# Mk3_Prototype2.net
KiCad netlist of a schematic drawn in EAGLE
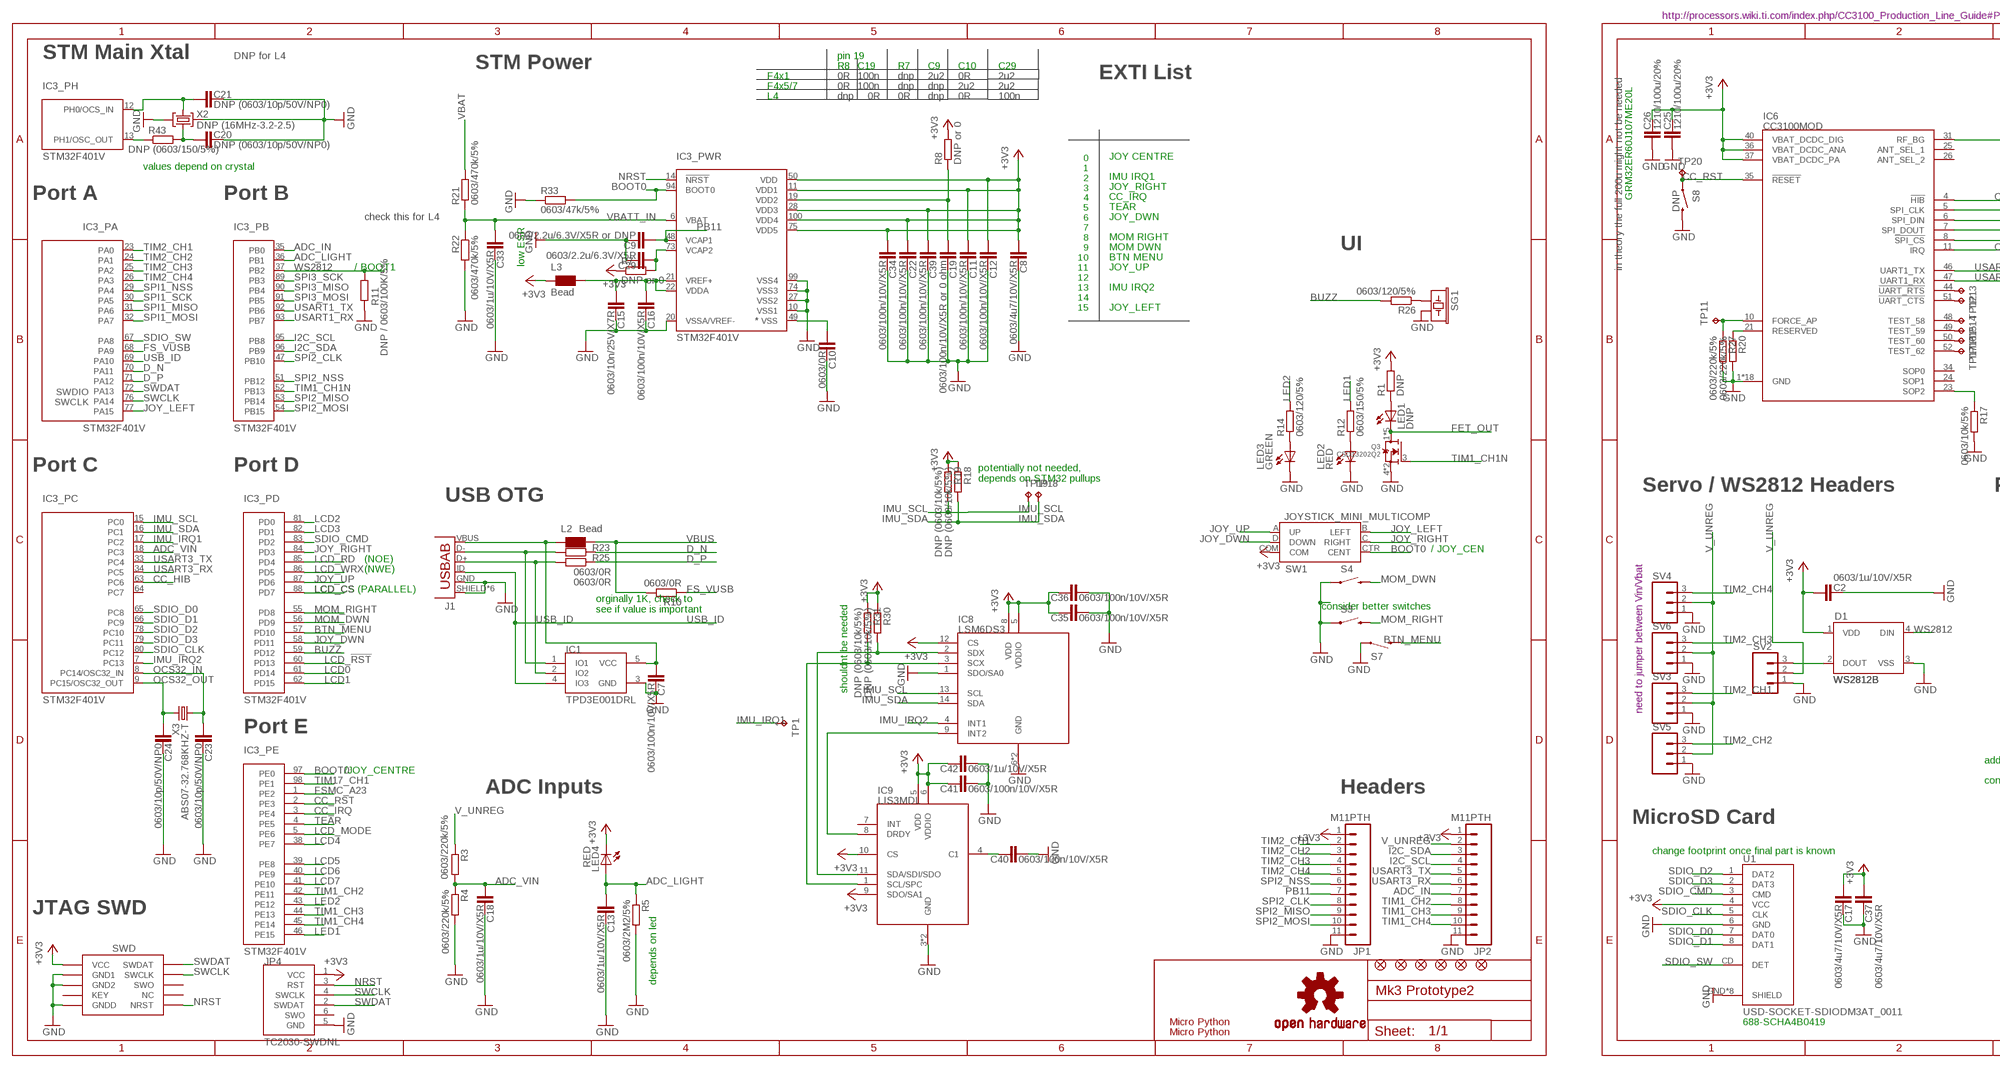
[diagram p0: schematic, sheet 1, part 1 of 2]
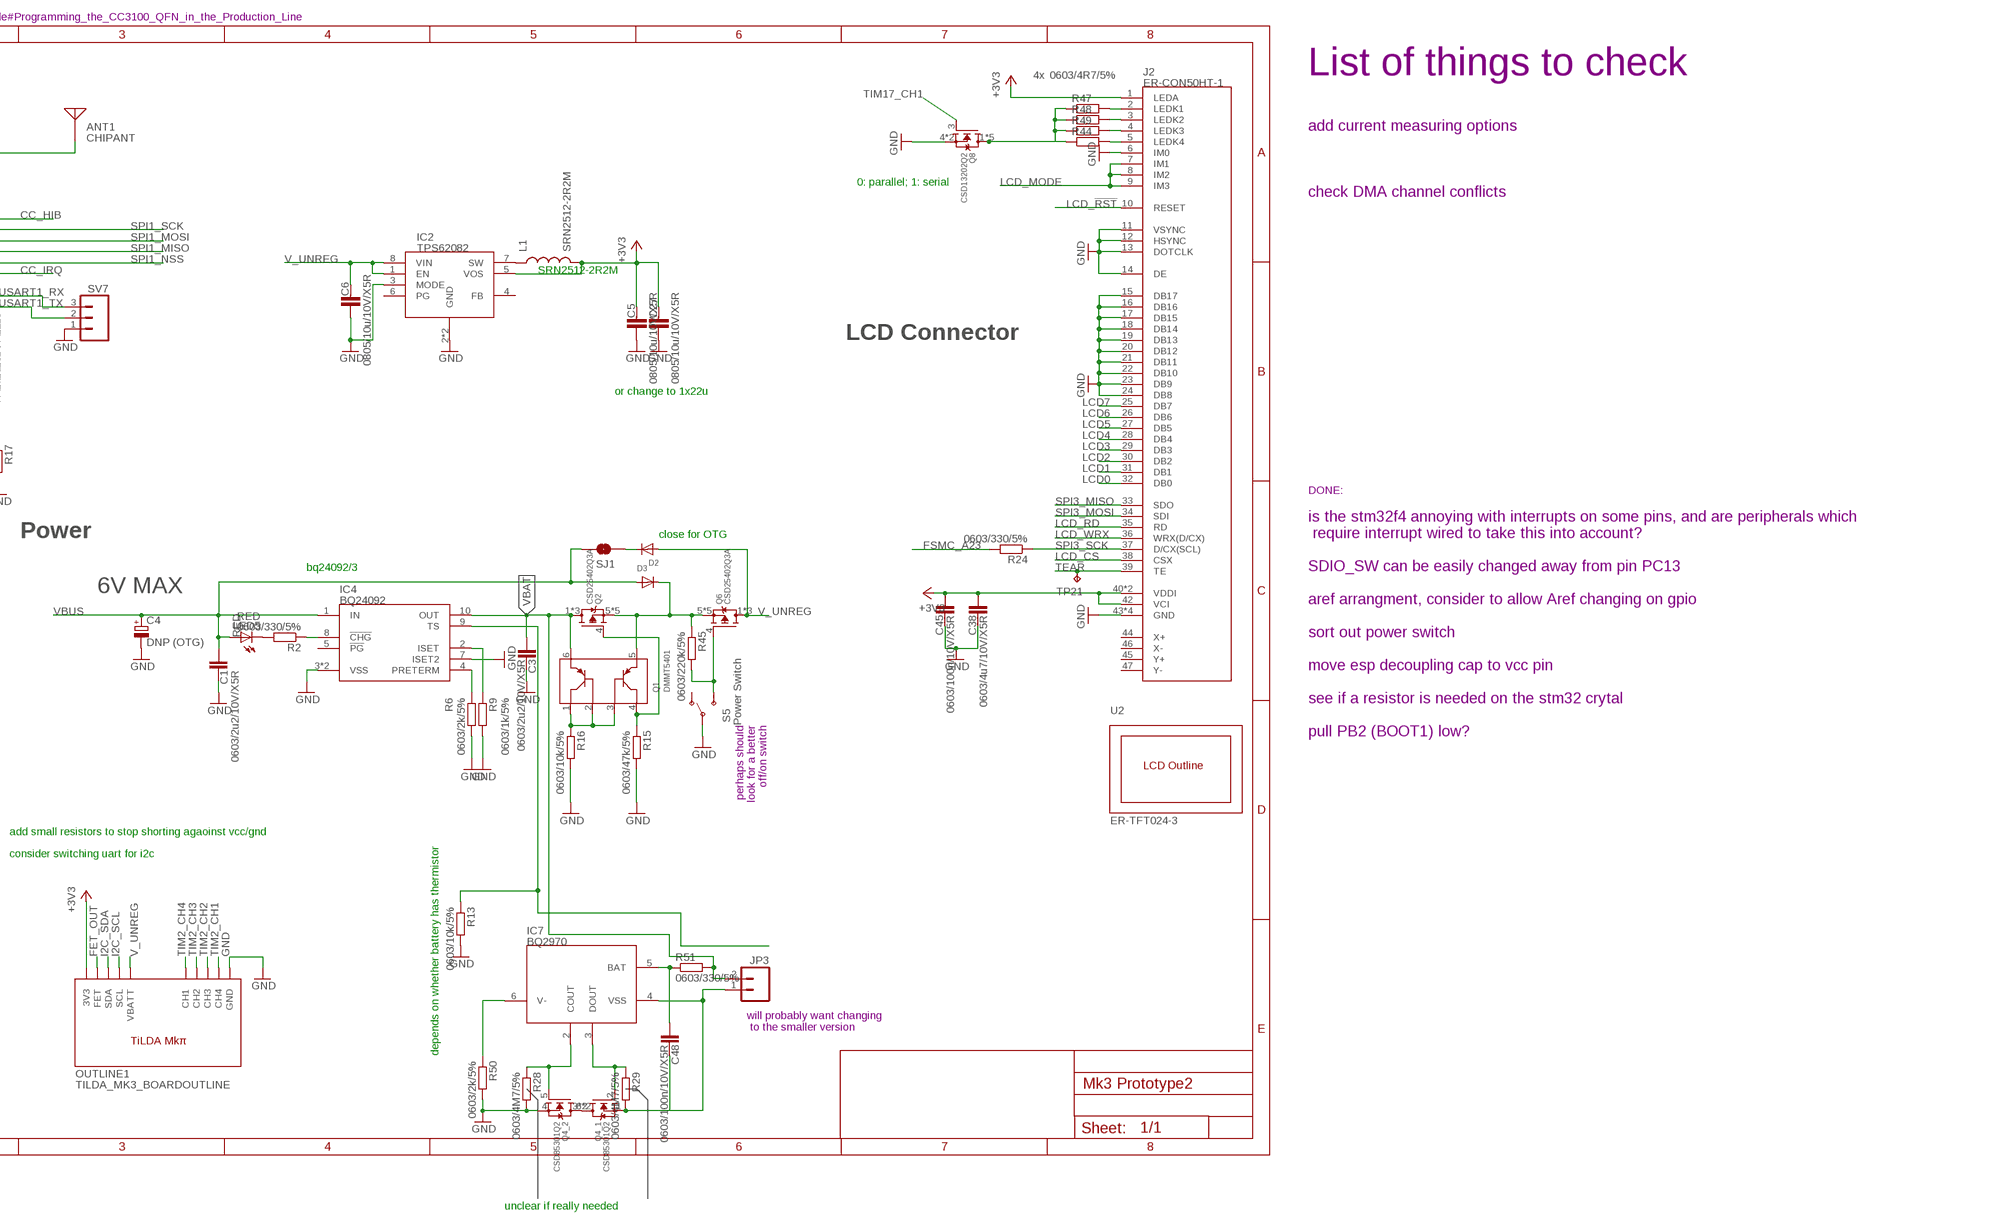
[diagram p1: schematic, sheet 1, part 2 of 2]

(export (version "E")
  (design (tool "Eeschema 10.0.6"))
  (components
    (comp (ref "ANT1")
      (value "CHIPANT")
      (footprint "eagle-import:2450AT42A100")
      (libsource (lib "eagle-import") (part "CHIPANT"))
    )
    (comp (ref "C1")
      (value "0603/2u2/10V/X5R")
      (footprint "eagle-import:C0603K-SMALL")
      (libsource (lib "eagle-import") (part "C-EUC0603K-SMALL"))
    )
    (comp (ref "C2")
      (value "0603/1u/10V/X5R")
      (footprint "eagle-import:C0603K-SMALL")
      (libsource (lib "eagle-import") (part "C-EUC0603K-SMALL"))
    )
    (comp (ref "C3")
      (value "0603/2u2/10V/X5R")
      (footprint "eagle-import:C0603K-SMALL")
      (libsource (lib "eagle-import") (part "C-EUC0603K-SMALL"))
    )
    (comp (ref "C4")
      (value "DNP (OTG)")
      (footprint "eagle-import:E2,5-6")
      (libsource (lib "eagle-import") (part "CPOL-EUE2.5-6"))
    )
    (comp (ref "C5")
      (value "0805/10u/10V/X5R")
      (footprint "eagle-import:C0805-N")
      (libsource (lib "eagle-import") (part "CAPACITOR0805-N"))
    )
    (comp (ref "C6")
      (value "0805/10u/10V/X5R")
      (footprint "eagle-import:C0805-N")
      (libsource (lib "eagle-import") (part "CAPACITOR0805-N"))
    )
    (comp (ref "C7")
      (value "0603/100n/10V/X5R")
      (footprint "eagle-import:C0603K-SMALL")
      (libsource (lib "eagle-import") (part "C-EUC0603K-SMALL"))
    )
    (comp (ref "C8")
      (value "0603/4u7/10V/X5R")
      (footprint "eagle-import:C0603K-SMALL")
      (libsource (lib "eagle-import") (part "C-EUC0603K-SMALL"))
    )
    (comp (ref "C9")
      (value "0603/2.2u/6.3V/X5R or DNP")
      (footprint "eagle-import:C0603K-SMALL")
      (libsource (lib "eagle-import") (part "C-EUC0603K-SMALL"))
    )
    (comp (ref "C10")
      (value "0603/0R")
      (footprint "eagle-import:C0603K-SMALL")
      (libsource (lib "eagle-import") (part "C-EUC0603K-SMALL"))
    )
    (comp (ref "C11")
      (value "0603/100n/10V/X5R")
      (footprint "eagle-import:C0603K-SMALL")
      (libsource (lib "eagle-import") (part "C-EUC0603K-SMALL"))
    )
    (comp (ref "C12")
      (value "0603/100n/10V/X5R")
      (footprint "eagle-import:C0603K-SMALL")
      (libsource (lib "eagle-import") (part "C-EUC0603K-SMALL"))
    )
    (comp (ref "C13")
      (value "0603/1u/10V/X5R")
      (footprint "eagle-import:C0603K-SMALL")
      (libsource (lib "eagle-import") (part "C-EUC0603K-SMALL"))
    )
    (comp (ref "C15")
      (value "0603/10n/25V/X7R")
      (footprint "eagle-import:C0603K-SMALL")
      (libsource (lib "eagle-import") (part "C-EUC0603K-SMALL"))
    )
    (comp (ref "C16")
      (value "0603/100n/10V/X5R")
      (footprint "eagle-import:C0603K-SMALL")
      (libsource (lib "eagle-import") (part "C-EUC0603K-SMALL"))
    )
    (comp (ref "C17")
      (value "0603/4u7/10V/X5R")
      (footprint "eagle-import:C0603K-SMALL")
      (libsource (lib "eagle-import") (part "C-EUC0603K-SMALL"))
    )
    (comp (ref "C18")
      (value "0603/1u/10V/X5R")
      (footprint "eagle-import:C0603K-SMALL")
      (libsource (lib "eagle-import") (part "C-EUC0603K-SMALL"))
    )
    (comp (ref "C19")
      (value "0603/100n/10V/X5R or 0 ohm")
      (footprint "eagle-import:C0603K-SMALL")
      (libsource (lib "eagle-import") (part "C-EUC0603K-SMALL"))
    )
    (comp (ref "C20")
      (value "DNP (0603/10p/50V/NP0)")
      (footprint "eagle-import:C0603K-SMALL")
      (libsource (lib "eagle-import") (part "C-EUC0603K-SMALL"))
    )
    (comp (ref "C21")
      (value "DNP (0603/10p/50V/NP0)")
      (footprint "eagle-import:C0603K-SMALL")
      (libsource (lib "eagle-import") (part "C-EUC0603K-SMALL"))
    )
    (comp (ref "C22")
      (value "0603/100n/10V/X5R")
      (footprint "eagle-import:C0603K-SMALL")
      (libsource (lib "eagle-import") (part "C-EUC0603K-SMALL"))
    )
    (comp (ref "C23")
      (value "0603/10p/50V/NP0")
      (footprint "eagle-import:C0603K-SMALL")
      (libsource (lib "eagle-import") (part "C-EUC0603K-SMALL"))
    )
    (comp (ref "C24")
      (value "0603/10p/50V/NP0")
      (footprint "eagle-import:C0603K-SMALL")
      (libsource (lib "eagle-import") (part "C-EUC0603K-SMALL"))
    )
    (comp (ref "C25")
      (value "1210/100u/20%")
      (footprint "eagle-import:C1210K")
      (libsource (lib "eagle-import") (part "C-EUC1210K"))
    )
    (comp (ref "C26")
      (value "1210/100u/20%")
      (footprint "eagle-import:C1210K")
      (libsource (lib "eagle-import") (part "C-EUC1210K"))
    )
    (comp (ref "C27")
      (value "0805/10u/10V/X5R")
      (footprint "eagle-import:C0805-N")
      (libsource (lib "eagle-import") (part "CAPACITOR0805-N"))
    )
    (comp (ref "C29")
      (value "0603/2.2u/6.3V/X5R")
      (footprint "eagle-import:C0603K-SMALL")
      (libsource (lib "eagle-import") (part "C-EUC0603K-SMALL"))
    )
    (comp (ref "C33")
      (value "0603/1u/10V/X5R")
      (footprint "eagle-import:C0603K-SMALL")
      (libsource (lib "eagle-import") (part "C-EUC0603K-SMALL"))
    )
    (comp (ref "C34")
      (value "0603/100n/10V/X5R")
      (footprint "eagle-import:C0603K-SMALL")
      (libsource (lib "eagle-import") (part "C-EUC0603K-SMALL"))
    )
    (comp (ref "C35")
      (value "0603/100n/10V/X5R")
      (footprint "eagle-import:C0603K-SMALL")
      (libsource (lib "eagle-import") (part "C-EUC0603K-SMALL"))
    )
    (comp (ref "C36")
      (value "0603/100n/10V/X5R")
      (footprint "eagle-import:C0603K-SMALL")
      (libsource (lib "eagle-import") (part "C-EUC0603K-SMALL"))
    )
    (comp (ref "C37")
      (value "0603/4u7/10V/X5R")
      (footprint "eagle-import:C0603K-SMALL")
      (libsource (lib "eagle-import") (part "C-EUC0603K-SMALL"))
    )
    (comp (ref "C38")
      (value "0603/4u7/10V/X5R")
      (footprint "eagle-import:C0603K-SMALL")
      (libsource (lib "eagle-import") (part "C-EUC0603K-SMALL"))
    )
    (comp (ref "C39")
      (value "0603/100n/10V/X5R")
      (footprint "eagle-import:C0603K-SMALL")
      (libsource (lib "eagle-import") (part "C-EUC0603K-SMALL"))
    )
    (comp (ref "C40")
      (value "0603/100n/10V/X5R")
      (footprint "eagle-import:C0603K-SMALL")
      (libsource (lib "eagle-import") (part "C-EUC0603K-SMALL"))
    )
    (comp (ref "C41")
      (value "0603/100n/10V/X5R")
      (footprint "eagle-import:C0603K-SMALL")
      (libsource (lib "eagle-import") (part "C-EUC0603K-SMALL"))
    )
    (comp (ref "C42")
      (value "0603/1u/10V/X5R")
      (footprint "eagle-import:C0603K-SMALL")
      (libsource (lib "eagle-import") (part "C-EUC0603K-SMALL"))
    )
    (comp (ref "C45")
      (value "0603/100n/10V/X5R")
      (footprint "eagle-import:C0603K-SMALL")
      (libsource (lib "eagle-import") (part "C-EUC0603K-SMALL"))
    )
    (comp (ref "C48")
      (value "0603/100n/10V/X5R")
      (footprint "eagle-import:C0603K-SMALL")
      (libsource (lib "eagle-import") (part "C-EUC0603K-SMALL"))
    )
    (comp (ref "D1")
      (value "WS2812B")
      (footprint "eagle-import:WS2812B")
      (libsource (lib "eagle-import") (part "WS2812B"))
    )
    (comp (ref "D2")
      (value "DIODESOD-323F")
      (footprint "eagle-import:SOD-323F")
      (libsource (lib "eagle-import") (part "DIODESOD-323F"))
    )
    (comp (ref "D3")
      (value "DIODESOD-323F")
      (footprint "eagle-import:SOD-323F")
      (libsource (lib "eagle-import") (part "DIODESOD-323F"))
    )
    (comp (ref "FID1")
      (value "FIDUCIAL1X2.5-STOP")
      (footprint "eagle-import:FIDUCIAL-1X2.5-STOP")
      (libsource (lib "eagle-import") (part "FIDUCIAL1X2.5-STOP"))
    )
    (comp (ref "FID2")
      (value "FIDUCIAL1X2.5-STOP")
      (footprint "eagle-import:FIDUCIAL-1X2.5-STOP")
      (libsource (lib "eagle-import") (part "FIDUCIAL1X2.5-STOP"))
    )
    (comp (ref "FID3")
      (value "FIDUCIAL1X2.5-STOP")
      (footprint "eagle-import:FIDUCIAL-1X2.5-STOP")
      (libsource (lib "eagle-import") (part "FIDUCIAL1X2.5-STOP"))
    )
    (comp (ref "FID4")
      (value "FIDUCIAL1X2.5-STOP")
      (footprint "eagle-import:FIDUCIAL-1X2.5-STOP")
      (libsource (lib "eagle-import") (part "FIDUCIAL1X2.5-STOP"))
    )
    (comp (ref "FID5")
      (value "FIDUCIAL1X2.5-STOP")
      (footprint "eagle-import:FIDUCIAL-1X2.5-STOP")
      (libsource (lib "eagle-import") (part "FIDUCIAL1X2.5-STOP"))
    )
    (comp (ref "FID6")
      (value "FIDUCIAL1X2.5-STOP")
      (footprint "eagle-import:FIDUCIAL-1X2.5-STOP")
      (libsource (lib "eagle-import") (part "FIDUCIAL1X2.5-STOP"))
    )
    (comp (ref "IC1")
      (value "TPD3E001DRL")
      (footprint "eagle-import:DRL-5")
      (libsource (lib "eagle-import") (part "TPD3E001DRL"))
    )
    (comp (ref "IC2")
      (value "TPS62082")
      (footprint "eagle-import:WSON8")
      (libsource (lib "eagle-import") (part "TPS62082"))
    )
    (comp (ref "IC3")
      (value "STM32F401V")
      (footprint "eagle-import:TQFP100")
      (fields (field (name "FARNELL") "2432116"))
      (libsource (lib "eagle-import") (part "STM32F401V"))
    )
    (comp (ref "IC4")
      (value "BQ24092")
      (footprint "eagle-import:HVSSOP10")
      (libsource (lib "eagle-import") (part "BQ2409X"))
    )
    (comp (ref "IC6")
      (value "CC3100MOD")
      (footprint "eagle-import:CC3100MOD")
      (libsource (lib "eagle-import") (part "CC3100MOD"))
    )
    (comp (ref "IC7")
      (value "BQ2970")
      (footprint "eagle-import:WSON-6")
      (libsource (lib "eagle-import") (part "BQ2970"))
    )
    (comp (ref "IC8")
      (value "LSM6DS3")
      (footprint "eagle-import:LGA14")
      (libsource (lib "eagle-import") (part "LSM6DS3"))
    )
    (comp (ref "IC9")
      (value "LIS3MDL")
      (footprint "eagle-import:LGA12")
      (libsource (lib "eagle-import") (part "LIS3MDL"))
    )
    (comp (ref "J1")
      (value "ZX62-AB-5PA(11)")
      (footprint "eagle-import:USB-AB-MICRO-SMD_LWK")
      (libsource (lib "eagle-import") (part "USB-AB-LWK"))
    )
    (comp (ref "J2")
      (value "ER-CON50HT-1")
      (footprint "eagle-import:FH12-50S-0.5SH")
      (libsource (lib "eagle-import") (part "ER-TFT024-3"))
    )
    (comp (ref "J3")
      (value "SWD_SHROUD")
      (footprint "eagle-import:SWD_PTH_SHROUD")
      (libsource (lib "eagle-import") (part "SWD_SHROUD"))
    )
    (comp (ref "JP1")
      (value "M11PTH")
      (footprint "eagle-import:1X11")
      (libsource (lib "eagle-import") (part "M11PTH"))
    )
    (comp (ref "JP2")
      (value "M11PTH")
      (footprint "eagle-import:1X11")
      (libsource (lib "eagle-import") (part "M11PTH"))
    )
    (comp (ref "JP3")
      (value "M02-JST-2MM-SMT")
      (footprint "eagle-import:JST-2-SMD")
      (libsource (lib "eagle-import") (part "M02-JST-2MM-SMT"))
    )
    (comp (ref "JP4")
      (value "TC2030-SWDNL")
      (footprint "eagle-import:TC2030-MCP-NL")
      (libsource (lib "eagle-import") (part "TC2030-SWDNL"))
    )
    (comp (ref "L1")
      (value "SRN2512-2R2M")
      (footprint "eagle-import:1008")
      (libsource (lib "eagle-import") (part "INDUCTOR1008"))
    )
    (comp (ref "L2")
      (value "Bead")
      (footprint "eagle-import:WUERTH-0805")
      (libsource (lib "eagle-import") (part "WE-CBF_0805"))
    )
    (comp (ref "L3")
      (value "Bead")
      (footprint "eagle-import:WUERTH-0805")
      (libsource (lib "eagle-import") (part "WE-CBF_0805"))
    )
    (comp (ref "LED1")
      (value "DNP")
      (footprint "eagle-import:LED5MM")
      (libsource (lib "eagle-import") (part "LED5MM"))
    )
    (comp (ref "LED2")
      (value "RED")
      (footprint "eagle-import:LED-0603-CORRECT")
      (fields (field (name "COLOUR") "RED"))
      (libsource (lib "eagle-import") (part "LED0603-CORRECT"))
    )
    (comp (ref "LED3")
      (value "GREEN")
      (footprint "eagle-import:LED-0603-CORRECT")
      (fields (field (name "COLOUR") "GREEN"))
      (libsource (lib "eagle-import") (part "LED0603-CORRECT"))
    )
    (comp (ref "LED4")
      (value "RED")
      (footprint "eagle-import:LED-0603-CORRECT")
      (libsource (lib "eagle-import") (part "LED0603-CORRECT"))
    )
    (comp (ref "LED5")
      (value "RED")
      (footprint "eagle-import:LED-0603-CORRECT")
      (fields (field (name "COLOUR") "RED"))
      (libsource (lib "eagle-import") (part "LED0603-CORRECT"))
    )
    (comp (ref "LOGO1")
      (value "OSHW-LOGOM")
      (footprint "eagle-import:OSHW-LOGO-M")
      (libsource (lib "eagle-import") (part "OSHW-LOGOM"))
    )
    (comp (ref "LOGO2")
      (value "MICROPYTHON-SILK")
      (footprint "eagle-import:UPYTHON_LOGO_SLIKONLY")
      (libsource (lib "eagle-import") (part "MICROPYTHON-SILK"))
    )
    (comp (ref "LOGO3")
      (value "MICROPYTHON-STOP")
      (footprint "eagle-import:UPYTHON_LOGO_STOPONLY")
      (libsource (lib "eagle-import") (part "MICROPYTHON-STOP"))
    )
    (comp (ref "OUTLINE1")
      (value "TILDA_MK3_BOARDOUTLINE")
      (footprint "eagle-import:TILDA_MKE_OUTLINE")
      (libsource (lib "eagle-import") (part "TILDA_MK3_BOARDOUTLINE"))
    )
    (comp (ref "Q1")
      (value "DMMT5401")
      (footprint "eagle-import:SOT26")
      (libsource (lib "eagle-import") (part "DMMT5401"))
    )
    (comp (ref "Q2")
      (value "CSD25402Q3A")
      (footprint "eagle-import:Q3A")
      (libsource (lib "eagle-import") (part "CSD25402Q3A"))
    )
    (comp (ref "Q3")
      (value "CSD13202Q2")
      (footprint "eagle-import:Q2")
      (libsource (lib "eagle-import") (part "CSD13202Q2"))
    )
    (comp (ref "Q4")
      (value "CSD85301Q2")
      (footprint "eagle-import:Q2_DUAL")
      (fields (field (name "FARNELL") "2470183"))
      (libsource (lib "eagle-import") (part "CSD85301Q2"))
    )
    (comp (ref "Q6")
      (value "CSD25402Q3A")
      (footprint "eagle-import:Q3A")
      (libsource (lib "eagle-import") (part "CSD25402Q3A"))
    )
    (comp (ref "Q8")
      (value "CSD13202Q2")
      (footprint "eagle-import:Q2")
      (libsource (lib "eagle-import") (part "CSD13202Q2"))
    )
    (comp (ref "R1")
      (value "DNP")
      (footprint "eagle-import:0207_10")
      (libsource (lib "eagle-import") (part "R-EU_0207/10"))
    )
    (comp (ref "R2")
      (value "0603/330/5%")
      (footprint "eagle-import:C0603K-SMALL")
      (libsource (lib "eagle-import") (part "R-EU_0603K-SMALL"))
    )
    (comp (ref "R3")
      (value "0603/220k/5%")
      (footprint "eagle-import:C0603K-SMALL")
      (libsource (lib "eagle-import") (part "R-EU_0603K-SMALL"))
    )
    (comp (ref "R4")
      (value "0603/220k/5%")
      (footprint "eagle-import:C0603K-SMALL")
      (libsource (lib "eagle-import") (part "R-EU_0603K-SMALL"))
    )
    (comp (ref "R5")
      (value "0603/2M2/5%")
      (footprint "eagle-import:C0603K-SMALL")
      (libsource (lib "eagle-import") (part "R-EU_0603K-SMALL"))
    )
    (comp (ref "R6")
      (value "0603/2k/5%")
      (footprint "eagle-import:C0603K-SMALL")
      (libsource (lib "eagle-import") (part "R-EU_0603K-SMALL"))
    )
    (comp (ref "R7")
      (value "DNP or 0")
      (footprint "eagle-import:C0603K-SMALL")
      (libsource (lib "eagle-import") (part "R-EU_0603K-SMALL"))
    )
    (comp (ref "R8")
      (value "DNP or 0")
      (footprint "eagle-import:C0603K-SMALL")
      (libsource (lib "eagle-import") (part "R-EU_0603K-SMALL"))
    )
    (comp (ref "R9")
      (value "0603/1k/5%")
      (footprint "eagle-import:C0603K-SMALL")
      (libsource (lib "eagle-import") (part "R-EU_0603K-SMALL"))
    )
    (comp (ref "R10")
      (value "0603/0R")
      (footprint "eagle-import:C0603K-SMALL")
      (libsource (lib "eagle-import") (part "R-EU_0603K-SMALL"))
    )
    (comp (ref "R11")
      (value "DNP / 0603/100K/5%")
      (footprint "eagle-import:C0603K-SMALL")
      (libsource (lib "eagle-import") (part "R-EU_0603K-SMALL"))
    )
    (comp (ref "R12")
      (value "0603/150/5%")
      (footprint "eagle-import:C0603K-SMALL")
      (libsource (lib "eagle-import") (part "R-EU_0603K-SMALL"))
    )
    (comp (ref "R13")
      (value "0603/10k/5%")
      (footprint "eagle-import:C0603K-SMALL")
      (libsource (lib "eagle-import") (part "R-EU_0603K-SMALL"))
    )
    (comp (ref "R14")
      (value "0603/120/5%")
      (footprint "eagle-import:C0603K-SMALL")
      (libsource (lib "eagle-import") (part "R-EU_0603K-SMALL"))
    )
    (comp (ref "R15")
      (value "0603/47k/5%")
      (footprint "eagle-import:C0603K-SMALL")
      (libsource (lib "eagle-import") (part "R-EU_0603K-SMALL"))
    )
    (comp (ref "R16")
      (value "0603/10k/5%")
      (footprint "eagle-import:C0603K-SMALL")
      (libsource (lib "eagle-import") (part "R-EU_0603K-SMALL"))
    )
    (comp (ref "R17")
      (value "0603/10k/5%")
      (footprint "eagle-import:C0603K-SMALL")
      (libsource (lib "eagle-import") (part "R-EU_0603K-SMALL"))
    )
    (comp (ref "R18")
      (value "DNP (0603/10k/5%)")
      (footprint "eagle-import:C0603K-SMALL")
      (libsource (lib "eagle-import") (part "R-EU_0603K-SMALL"))
    )
    (comp (ref "R19")
      (value "DNP (0603/10k/5%)")
      (footprint "eagle-import:C0603K-SMALL")
      (libsource (lib "eagle-import") (part "R-EU_0603K-SMALL"))
    )
    (comp (ref "R20")
      (value "0603/220k/5%")
      (footprint "eagle-import:C0603K-SMALL")
      (libsource (lib "eagle-import") (part "R-EU_0603K-SMALL"))
    )
    (comp (ref "R21")
      (value "0603/470k/5%")
      (footprint "eagle-import:C0603K-SMALL")
      (libsource (lib "eagle-import") (part "R-EU_0603K-SMALL"))
    )
    (comp (ref "R22")
      (value "0603/470k/5%")
      (footprint "eagle-import:C0603K-SMALL")
      (libsource (lib "eagle-import") (part "R-EU_0603K-SMALL"))
    )
    (comp (ref "R23")
      (value "0603/0R")
      (footprint "eagle-import:C0603K-SMALL")
      (libsource (lib "eagle-import") (part "R-EU_0603K-SMALL"))
    )
    (comp (ref "R24")
      (value "0603/330/5%")
      (footprint "eagle-import:C0603K-SMALL")
      (libsource (lib "eagle-import") (part "R-EU_0603K-SMALL"))
    )
    (comp (ref "R25")
      (value "0603/0R")
      (footprint "eagle-import:C0603K-SMALL")
      (libsource (lib "eagle-import") (part "R-EU_0603K-SMALL"))
    )
    (comp (ref "R26")
      (value "0603/120/5%")
      (footprint "eagle-import:C0603K-SMALL")
      (libsource (lib "eagle-import") (part "R-EU_0603K-SMALL"))
    )
    (comp (ref "R27")
      (value "0603/220k/5%")
      (footprint "eagle-import:C0603K-SMALL")
      (libsource (lib "eagle-import") (part "R-EU_0603K-SMALL"))
    )
    (comp (ref "R28")
      (value "0603/4M7/5%")
      (footprint "eagle-import:C0603K-SMALL")
      (libsource (lib "eagle-import") (part "R-EU_0603K-SMALL"))
    )
    (comp (ref "R29")
      (value "0603/4M7/5%")
      (footprint "eagle-import:C0603K-SMALL")
      (libsource (lib "eagle-import") (part "R-EU_0603K-SMALL"))
    )
    (comp (ref "R30")
      (value "DNP (0603/10k/5%)")
      (footprint "eagle-import:C0603K-SMALL")
      (libsource (lib "eagle-import") (part "R-EU_0603K-SMALL"))
    )
    (comp (ref "R31")
      (value "DNP (0603/10k/5%)")
      (footprint "eagle-import:C0603K-SMALL")
      (libsource (lib "eagle-import") (part "R-EU_0603K-SMALL"))
    )
    (comp (ref "R33")
      (value "0603/47k/5%")
      (footprint "eagle-import:C0603K-SMALL")
      (libsource (lib "eagle-import") (part "R-EU_0603K-SMALL"))
    )
    (comp (ref "R43")
      (value "DNP (0603/150/5%)")
      (footprint "eagle-import:C0603K-SMALL")
      (libsource (lib "eagle-import") (part "R-EU_0603K-SMALL"))
    )
    (comp (ref "R44")
      (value "0603/4R7/5%")
      (footprint "eagle-import:C0603K-SMALL")
      (libsource (lib "eagle-import") (part "R-EU_0603K-SMALL"))
    )
    (comp (ref "R45")
      (value "0603/220k/5%")
      (footprint "eagle-import:C0603K-SMALL")
      (libsource (lib "eagle-import") (part "R-EU_0603K-SMALL"))
    )
    (comp (ref "R47")
      (value "0603/4R7/5%")
      (footprint "eagle-import:C0603K-SMALL")
      (libsource (lib "eagle-import") (part "R-EU_0603K-SMALL"))
    )
    (comp (ref "R48")
      (value "0603/4R7/5%")
      (footprint "eagle-import:C0603K-SMALL")
      (libsource (lib "eagle-import") (part "R-EU_0603K-SMALL"))
    )
    (comp (ref "R49")
      (value "0603/4R7/5%")
      (footprint "eagle-import:C0603K-SMALL")
      (libsource (lib "eagle-import") (part "R-EU_0603K-SMALL"))
    )
    (comp (ref "R50")
      (value "0603/2k/5%")
      (footprint "eagle-import:C0603K-SMALL")
      (libsource (lib "eagle-import") (part "R-EU_0603K-SMALL"))
    )
    (comp (ref "R51")
      (value "0603/330/5%")
      (footprint "eagle-import:C0603K-SMALL")
      (libsource (lib "eagle-import") (part "R-EU_0603K-SMALL"))
    )
    (comp (ref "S3")
      (value "1217769")
      (footprint "eagle-import:TACTILE_SWITCH_TALL")
      (libsource (lib "eagle-import") (part "SWITCH-MOMENTARY-2"))
    )
    (comp (ref "S4")
      (value "1217769")
      (footprint "eagle-import:TACTILE_SWITCH_TALL")
      (libsource (lib "eagle-import") (part "SWITCH-MOMENTARY-2"))
    )
    (comp (ref "S5")
      (value "Power Switch")
      (footprint "eagle-import:SWITCH-SPST-SMD-A")
      (libsource (lib "eagle-import") (part "SWITCH-SPST-SMD-A"))
    )
    (comp (ref "S7")
      (value "SWITCH-MOMENTARY-2SMD-1101NE")
      (footprint "eagle-import:TACTILE-SWITCH-1101NE")
      (libsource (lib "eagle-import") (part "SWITCH-MOMENTARY-2SMD-1101NE"))
    )
    (comp (ref "S8")
      (value "DNP")
      (footprint "eagle-import:TACTILE-SWITCH-1101NE")
      (libsource (lib "eagle-import") (part "SWITCH-MOMENTARY-2SMD-1101NE"))
    )
    (comp (ref "SG1")
      (value "BUZZER-PKLCS1212E")
      (footprint "eagle-import:BUZZER-PKLCS1212E")
      (libsource (lib "eagle-import") (part "BUZZER-PKLCS1212E"))
    )
    (comp (ref "SJ1")
      (value "JUMPER-PAD-2-NOYES_SILK")
      (footprint "eagle-import:PAD-JUMPER-2-NO_YES_SILK")
      (libsource (lib "eagle-import") (part "JUMPER-PAD-2-NOYES_SILK"))
    )
    (comp (ref "SV2")
      (value "M03PTH")
      (footprint "eagle-import:1X03")
      (libsource (lib "eagle-import") (part "M03PTH"))
    )
    (comp (ref "SV3")
      (value "M03PTH")
      (footprint "eagle-import:1X03")
      (libsource (lib "eagle-import") (part "M03PTH"))
    )
    (comp (ref "SV4")
      (value "M03PTH")
      (footprint "eagle-import:1X03")
      (libsource (lib "eagle-import") (part "M03PTH"))
    )
    (comp (ref "SV5")
      (value "M03PTH")
      (footprint "eagle-import:1X03")
      (libsource (lib "eagle-import") (part "M03PTH"))
    )
    (comp (ref "SV6")
      (value "M03PTH")
      (footprint "eagle-import:1X03")
      (libsource (lib "eagle-import") (part "M03PTH"))
    )
    (comp (ref "SV7")
      (value "M03PTH")
      (footprint "eagle-import:1X03")
      (libsource (lib "eagle-import") (part "M03PTH"))
    )
    (comp (ref "SW1")
      (value "JOYSTICK_MINI_MULTICOMP")
      (footprint "eagle-import:JOYSTICK_MULTICOMP")
      (libsource (lib "eagle-import") (part "JOYSTICK_MINI_MULTICOMP"))
    )
    (comp (ref "TP1")
      (value "TPB1,27")
      (footprint "eagle-import:B1,27")
      (libsource (lib "eagle-import") (part "TPB1,27"))
    )
    (comp (ref "TP11")
      (value "TPB1,27")
      (footprint "eagle-import:B1,27")
      (libsource (lib "eagle-import") (part "TPB1,27"))
    )
    (comp (ref "TP12")
      (value "TPB1,27")
      (footprint "eagle-import:B1,27")
      (libsource (lib "eagle-import") (part "TPB1,27"))
    )
    (comp (ref "TP13")
      (value "TPB1,27")
      (footprint "eagle-import:B1,27")
      (libsource (lib "eagle-import") (part "TPB1,27"))
    )
    (comp (ref "TP14")
      (value "TPB1,27")
      (footprint "eagle-import:B1,27")
      (libsource (lib "eagle-import") (part "TPB1,27"))
    )
    (comp (ref "TP15")
      (value "TPB1,27")
      (footprint "eagle-import:B1,27")
      (libsource (lib "eagle-import") (part "TPB1,27"))
    )
    (comp (ref "TP16")
      (value "TPB1,27")
      (footprint "eagle-import:B1,27")
      (libsource (lib "eagle-import") (part "TPB1,27"))
    )
    (comp (ref "TP17")
      (value "TPB1,27")
      (footprint "eagle-import:B1,27")
      (libsource (lib "eagle-import") (part "TPB1,27"))
    )
    (comp (ref "TP18")
      (value "TPB1,27")
      (footprint "eagle-import:B1,27")
      (libsource (lib "eagle-import") (part "TPB1,27"))
    )
    (comp (ref "TP19")
      (value "TPB1,27")
      (footprint "eagle-import:B1,27")
      (libsource (lib "eagle-import") (part "TPB1,27"))
    )
    (comp (ref "TP20")
      (value "TPB1,27")
      (footprint "eagle-import:B1,27")
      (libsource (lib "eagle-import") (part "TPB1,27"))
    )
    (comp (ref "TP21")
      (value "TPB1,27")
      (footprint "eagle-import:B1,27")
      (libsource (lib "eagle-import") (part "TPB1,27"))
    )
    (comp (ref "U1")
      (value "USD-SOCKET-SDIODM3AT_0011")
      (footprint "eagle-import:DM3AT_0011")
      (libsource (lib "eagle-import") (part "USD-SOCKET-SDIODM3AT_0011"))
    )
    (comp (ref "U2")
      (value "ER-TFT024-3")
      (footprint "eagle-import:ER-TFT024-3")
      (libsource (lib "eagle-import") (part "ER-TFT024-3-OUTLINE"))
    )
    (comp (ref "X2")
      (value "DNP (16MHz-3.2-2.5)")
      (footprint "eagle-import:CRYSTAL-3.2-2.5")
      (libsource (lib "eagle-import") (part "CRYSTAL-3.2-2.5"))
    )
    (comp (ref "X3")
      (value "ABS07-32.768KHZ-T")
      (footprint "eagle-import:RESONATOR_EPSON_FC_145")
      (libsource (lib "eagle-import") (part "RESONATOR_EPSON_FC_145"))
    )
  )
  (nets
    (net (code "1") (name "+3V3") (class "Default")
      (node (ref "C11") (pin "2") (pinfunction "2_2") (pintype "passive"))
      (node (ref "C12") (pin "2") (pinfunction "2_2") (pintype "passive"))
      (node (ref "C17") (pin "2") (pinfunction "2_2") (pintype "passive"))
      (node (ref "C2") (pin "2") (pinfunction "2_2") (pintype "passive"))
      (node (ref "C22") (pin "2") (pinfunction "2_2") (pintype "passive"))
      (node (ref "C25") (pin "1") (pinfunction "1_1") (pintype "passive"))
      (node (ref "C26") (pin "1") (pinfunction "1_1") (pintype "passive"))
      (node (ref "C27") (pin "1") (pinfunction "1_1") (pintype "passive"))
      (node (ref "C34") (pin "2") (pinfunction "2_2") (pintype "passive"))
      (node (ref "C35") (pin "1") (pinfunction "1_1") (pintype "passive"))
      (node (ref "C36") (pin "1") (pinfunction "1_1") (pintype "passive"))
      (node (ref "C37") (pin "2") (pinfunction "2_2") (pintype "passive"))
      (node (ref "C38") (pin "2") (pinfunction "2_2") (pintype "passive"))
      (node (ref "C39") (pin "2") (pinfunction "2_2") (pintype "passive"))
      (node (ref "C41") (pin "1") (pinfunction "1_1") (pintype "passive"))
      (node (ref "C42") (pin "1") (pinfunction "1_1") (pintype "passive"))
      (node (ref "C45") (pin "2") (pinfunction "2_2") (pintype "passive"))
      (node (ref "C5") (pin "1") (pinfunction "1_1") (pintype "passive"))
      (node (ref "C8") (pin "2") (pinfunction "2_2") (pintype "passive"))
      (node (ref "D1") (pin "1") (pinfunction "VDD_1") (pintype "power_in"))
      (node (ref "IC2") (pin "5") (pinfunction "VOS_5") (pintype "input"))
      (node (ref "IC3") (pin "100") (pinfunction "VDD4_100") (pintype "bidirectional"))
      (node (ref "IC3") (pin "11") (pinfunction "VDD1_11") (pintype "bidirectional"))
      (node (ref "IC3") (pin "28") (pinfunction "VDD3_28") (pintype "bidirectional"))
      (node (ref "IC3") (pin "50") (pinfunction "VDD_50") (pintype "bidirectional"))
      (node (ref "IC3") (pin "75") (pinfunction "VDD5_75") (pintype "bidirectional"))
      (node (ref "IC6") (pin "36") (pinfunction "VBAT_DCDC_ANA_36") (pintype "power_in"))
      (node (ref "IC6") (pin "37") (pinfunction "VBAT_DCDC_PA_37") (pintype "power_in"))
      (node (ref "IC6") (pin "40") (pinfunction "VBAT_DCDC_DIG_40") (pintype "power_in"))
      (node (ref "IC8") (pin "12") (pinfunction "CS_12") (pintype "input"))
      (node (ref "IC8") (pin "5") (pinfunction "VDDIO_5") (pintype "power_in"))
      (node (ref "IC8") (pin "8") (pinfunction "VDD_8") (pintype "power_in"))
      (node (ref "IC9") (pin "10") (pinfunction "CS_10") (pintype "input"))
      (node (ref "IC9") (pin "5") (pinfunction "VDD_5") (pintype "power_in"))
      (node (ref "IC9") (pin "6") (pinfunction "VDDIO_6") (pintype "power_in"))
      (node (ref "IC9") (pin "9") (pinfunction "SDO/SA1_9") (pintype "bidirectional"))
      (node (ref "J2") (pin "1") (pinfunction "LEDA_1") (pintype "passive"))
      (node (ref "J2") (pin "40") (pinfunction "VDDI_40") (pintype "power_in"))
      (node (ref "J2") (pin "41") (pinfunction "VDDI_41") (pintype "power_in"))
      (node (ref "J2") (pin "42") (pinfunction "VCI_42") (pintype "power_in"))
      (node (ref "J3") (pin "1") (pinfunction "VCC_1") (pintype "power_in"))
      (node (ref "JP1") (pin "1") (pinfunction "1_1") (pintype "passive"))
      (node (ref "JP2") (pin "1") (pinfunction "1_1") (pintype "passive"))
      (node (ref "JP4") (pin "1") (pinfunction "VCC_1") (pintype "power_in"))
      (node (ref "L1") (pin "2") (pinfunction "2_2") (pintype "passive"))
      (node (ref "L3") (pin "1") (pinfunction "1_1") (pintype "passive"))
      (node (ref "LED4") (pin "C") (pinfunction "C_C") (pintype "passive"))
      (node (ref "OUTLINE1") (pin "3V3") (pinfunction "3V3_3V3") (pintype "bidirectional"))
      (node (ref "R1") (pin "2") (pinfunction "2_2") (pintype "passive"))
      (node (ref "R18") (pin "1") (pinfunction "1_1") (pintype "passive"))
      (node (ref "R19") (pin "1") (pinfunction "1_1") (pintype "passive"))
      (node (ref "R30") (pin "1") (pinfunction "1_1") (pintype "passive"))
      (node (ref "R31") (pin "1") (pinfunction "1_1") (pintype "passive"))
      (node (ref "R7") (pin "1") (pinfunction "1_1") (pintype "passive"))
      (node (ref "R8") (pin "2") (pinfunction "2_2") (pintype "passive"))
      (node (ref "SW1") (pin "COM") (pinfunction "COM_COM") (pintype "bidirectional"))
      (node (ref "U1") (pin "4") (pinfunction "VCC_4") (pintype "bidirectional"))
    )
    (net (code "2") (name "/ADC_IN") (class "Default")
      (node (ref "IC3") (pin "35") (pinfunction "PB0_35") (pintype "bidirectional"))
      (node (ref "JP2") (pin "7") (pinfunction "7_7") (pintype "passive"))
    )
    (net (code "3") (name "/ADC_LIGHT") (class "Default")
      (node (ref "C13") (pin "2") (pinfunction "2_2") (pintype "passive"))
      (node (ref "IC3") (pin "36") (pinfunction "PB1_36") (pintype "bidirectional"))
      (node (ref "LED4") (pin "A") (pinfunction "A_A") (pintype "passive"))
      (node (ref "R5") (pin "1") (pinfunction "1_1") (pintype "passive"))
    )
    (net (code "4") (name "/ADC_VIN") (class "Default")
      (node (ref "C18") (pin "2") (pinfunction "2_2") (pintype "passive"))
      (node (ref "IC3") (pin "18") (pinfunction "PC3_18") (pintype "bidirectional"))
      (node (ref "R3") (pin "2") (pinfunction "2_2") (pintype "passive"))
      (node (ref "R4") (pin "1") (pinfunction "1_1") (pintype "passive"))
    )
    (net (code "5") (name "/BOOT0") (class "Default")
      (node (ref "IC3") (pin "94") (pinfunction "BOOT0_94") (pintype "bidirectional"))
      (node (ref "IC3") (pin "97") (pinfunction "PE0_97") (pintype "bidirectional"))
      (node (ref "R33") (pin "2") (pinfunction "2_2") (pintype "passive"))
      (node (ref "SW1") (pin "CTR") (pinfunction "CENT_CTR") (pintype "bidirectional"))
    )
    (net (code "6") (name "/BTN_MENU") (class "Default")
      (node (ref "IC3") (pin "57") (pinfunction "PD10_57") (pintype "bidirectional"))
      (node (ref "S7") (pin "2") (pinfunction "2_2") (pintype "passive"))
    )
    (net (code "7") (name "/BUZZ") (class "Default")
      (node (ref "IC3") (pin "59") (pinfunction "PD12_59") (pintype "bidirectional"))
      (node (ref "R26") (pin "2") (pinfunction "2_2") (pintype "passive"))
    )
    (net (code "8") (name "/CC_HIB") (class "Default")
      (node (ref "IC3") (pin "63") (pinfunction "PC6_63") (pintype "bidirectional"))
      (node (ref "IC6") (pin "4") (pinfunction "~{HIB}_4") (pintype "input"))
    )
    (net (code "9") (name "/CC_IRQ") (class "Default")
      (node (ref "IC3") (pin "3") (pinfunction "PE4_3") (pintype "bidirectional"))
      (node (ref "IC6") (pin "11") (pinfunction "IRQ_11") (pintype "output"))
    )
    (net (code "10") (name "/CC_RST") (class "Default")
      (node (ref "IC3") (pin "2") (pinfunction "PE3_2") (pintype "bidirectional"))
      (node (ref "IC6") (pin "35") (pinfunction "~{RESET}_35") (pintype "input"))
      (node (ref "S8") (pin "1") (pinfunction "1_1") (pintype "passive"))
      (node (ref "TP20") (pin "TP") (pinfunction "TP_TP") (pintype "input"))
    )
    (net (code "11") (name "/D_N") (class "Default")
      (node (ref "IC3") (pin "70") (pinfunction "PA11_70") (pintype "bidirectional"))
      (node (ref "R23") (pin "1") (pinfunction "1_1") (pintype "passive"))
    )
    (net (code "12") (name "/D_P") (class "Default")
      (node (ref "IC3") (pin "71") (pinfunction "PA12_71") (pintype "bidirectional"))
      (node (ref "R25") (pin "1") (pinfunction "1_1") (pintype "passive"))
    )
    (net (code "13") (name "/FET_OUT") (class "Default")
      (node (ref "LED1") (pin "K") (pinfunction "C_K") (pintype "passive"))
      (node (ref "OUTLINE1") (pin "FET") (pinfunction "FET_FET") (pintype "bidirectional"))
      (node (ref "Q3") (pin "1") (pinfunction "D_1") (pintype "bidirectional"))
      (node (ref "Q3") (pin "2") (pinfunction "D_2") (pintype "bidirectional"))
      (node (ref "Q3") (pin "5") (pinfunction "D_5") (pintype "bidirectional"))
      (node (ref "Q3") (pin "6") (pinfunction "D_6") (pintype "bidirectional"))
      (node (ref "Q3") (pin "EP1") (pinfunction "D_EP1") (pintype "bidirectional"))
    )
    (net (code "14") (name "/FSMC_A23") (class "Default")
      (node (ref "IC3") (pin "1") (pinfunction "PE2_1") (pintype "bidirectional"))
      (node (ref "R24") (pin "2") (pinfunction "2_2") (pintype "passive"))
    )
    (net (code "15") (name "/FS_VUSB") (class "Default")
      (node (ref "IC3") (pin "68") (pinfunction "PA9_68") (pintype "bidirectional"))
      (node (ref "R10") (pin "1") (pinfunction "1_1") (pintype "passive"))
    )
    (net (code "16") (name "/I2C_SCL") (class "Default")
      (node (ref "IC3") (pin "95") (pinfunction "PB8_95") (pintype "bidirectional"))
      (node (ref "JP2") (pin "4") (pinfunction "4_4") (pintype "passive"))
      (node (ref "OUTLINE1") (pin "SCL") (pinfunction "SCL_SCL") (pintype "bidirectional"))
    )
    (net (code "17") (name "/I2C_SDA") (class "Default")
      (node (ref "IC3") (pin "96") (pinfunction "PB9_96") (pintype "bidirectional"))
      (node (ref "JP2") (pin "3") (pinfunction "3_3") (pintype "passive"))
      (node (ref "OUTLINE1") (pin "SDA") (pinfunction "SDA_SDA") (pintype "bidirectional"))
    )
    (net (code "18") (name "/IMU_IRQ1") (class "Default")
      (node (ref "IC3") (pin "17") (pinfunction "PC2_17") (pintype "bidirectional"))
      (node (ref "TP1") (pin "TP") (pinfunction "TP_TP") (pintype "input"))
    )
    (net (code "19") (name "/IMU_IRQ2") (class "Default")
      (node (ref "IC3") (pin "7") (pinfunction "PC13_7") (pintype "bidirectional"))
      (node (ref "IC8") (pin "4") (pinfunction "INT1_4") (pintype "output"))
    )
    (net (code "20") (name "/IMU_SCL") (class "Default")
      (node (ref "IC3") (pin "15") (pinfunction "PC0_15") (pintype "bidirectional"))
      (node (ref "IC8") (pin "13") (pinfunction "SCL_13") (pintype "input"))
      (node (ref "R19") (pin "2") (pinfunction "2_2") (pintype "passive"))
      (node (ref "TP19") (pin "TP") (pinfunction "TP_TP") (pintype "input"))
    )
    (net (code "21") (name "/IMU_SDA") (class "Default")
      (node (ref "IC3") (pin "16") (pinfunction "PC1_16") (pintype "bidirectional"))
      (node (ref "IC8") (pin "14") (pinfunction "SDA_14") (pintype "open_collector"))
      (node (ref "R18") (pin "2") (pinfunction "2_2") (pintype "passive"))
      (node (ref "TP18") (pin "TP") (pinfunction "TP_TP") (pintype "input"))
    )
    (net (code "22") (name "/JOY_DWN") (class "Default")
      (node (ref "IC3") (pin "58") (pinfunction "PD11_58") (pintype "bidirectional"))
      (node (ref "SW1") (pin "D") (pinfunction "DOWN_D") (pintype "bidirectional"))
    )
    (net (code "23") (name "/JOY_LEFT") (class "Default")
      (node (ref "IC3") (pin "77") (pinfunction "PA15_77") (pintype "bidirectional"))
      (node (ref "SW1") (pin "B") (pinfunction "LEFT_B") (pintype "bidirectional"))
    )
    (net (code "24") (name "/JOY_RIGHT") (class "Default")
      (node (ref "IC3") (pin "84") (pinfunction "PD3_84") (pintype "bidirectional"))
      (node (ref "SW1") (pin "C") (pinfunction "RIGHT_C") (pintype "bidirectional"))
    )
    (net (code "25") (name "/JOY_UP") (class "Default")
      (node (ref "IC3") (pin "87") (pinfunction "PD6_87") (pintype "bidirectional"))
      (node (ref "SW1") (pin "A") (pinfunction "UP_A") (pintype "bidirectional"))
    )
    (net (code "26") (name "/LCD0") (class "Default")
      (node (ref "IC3") (pin "61") (pinfunction "PD14_61") (pintype "bidirectional"))
      (node (ref "J2") (pin "32") (pinfunction "DB0_32") (pintype "bidirectional"))
    )
    (net (code "27") (name "/LCD1") (class "Default")
      (node (ref "IC3") (pin "62") (pinfunction "PD15_62") (pintype "bidirectional"))
      (node (ref "J2") (pin "31") (pinfunction "DB1_31") (pintype "bidirectional"))
    )
    (net (code "28") (name "/LCD2") (class "Default")
      (node (ref "IC3") (pin "81") (pinfunction "PD0_81") (pintype "bidirectional"))
      (node (ref "J2") (pin "30") (pinfunction "DB2_30") (pintype "bidirectional"))
    )
    (net (code "29") (name "/LCD3") (class "Default")
      (node (ref "IC3") (pin "82") (pinfunction "PD1_82") (pintype "bidirectional"))
      (node (ref "J2") (pin "29") (pinfunction "DB3_29") (pintype "bidirectional"))
    )
    (net (code "30") (name "/LCD4") (class "Default")
      (node (ref "IC3") (pin "38") (pinfunction "PE7_38") (pintype "bidirectional"))
      (node (ref "J2") (pin "28") (pinfunction "DB4_28") (pintype "bidirectional"))
    )
    (net (code "31") (name "/LCD5") (class "Default")
      (node (ref "IC3") (pin "39") (pinfunction "PE8_39") (pintype "bidirectional"))
      (node (ref "J2") (pin "27") (pinfunction "DB5_27") (pintype "bidirectional"))
    )
    (net (code "32") (name "/LCD6") (class "Default")
      (node (ref "IC3") (pin "40") (pinfunction "PE9_40") (pintype "bidirectional"))
      (node (ref "J2") (pin "26") (pinfunction "DB6_26") (pintype "bidirectional"))
    )
    (net (code "33") (name "/LCD7") (class "Default")
      (node (ref "IC3") (pin "41") (pinfunction "PE10_41") (pintype "bidirectional"))
      (node (ref "J2") (pin "25") (pinfunction "DB7_25") (pintype "bidirectional"))
    )
    (net (code "34") (name "/LCD_CS") (class "Default")
      (node (ref "IC3") (pin "88") (pinfunction "PD7_88") (pintype "bidirectional"))
      (node (ref "J2") (pin "38") (pinfunction "CSX_38") (pintype "output"))
    )
    (net (code "35") (name "/LCD_MODE") (class "Default")
      (node (ref "IC3") (pin "5") (pinfunction "PE6_5") (pintype "bidirectional"))
      (node (ref "J2") (pin "7") (pinfunction "IM1_7") (pintype "input"))
      (node (ref "J2") (pin "8") (pinfunction "IM2_8") (pintype "input"))
      (node (ref "J2") (pin "9") (pinfunction "IM3_9") (pintype "input"))
    )
    (net (code "36") (name "/LCD_RD") (class "Default")
      (node (ref "IC3") (pin "85") (pinfunction "PD4_85") (pintype "bidirectional"))
      (node (ref "J2") (pin "35") (pinfunction "RD_35") (pintype "input"))
    )
    (net (code "37") (name "/LCD_WRX") (class "Default")
      (node (ref "IC3") (pin "86") (pinfunction "PD5_86") (pintype "bidirectional"))
      (node (ref "J2") (pin "36") (pinfunction "WRX(D/CX)_36") (pintype "input"))
    )
    (net (code "38") (name "/LCD_~{RST}") (class "Default")
      (node (ref "IC3") (pin "60") (pinfunction "PD13_60") (pintype "bidirectional"))
      (node (ref "J2") (pin "10") (pinfunction "RESET_10") (pintype "input"))
    )
    (net (code "39") (name "/LED1") (class "Default")
      (node (ref "IC3") (pin "46") (pinfunction "PE15_46") (pintype "bidirectional"))
      (node (ref "R12") (pin "2") (pinfunction "2_2") (pintype "passive"))
    )
    (net (code "40") (name "/LED2") (class "Default")
      (node (ref "IC3") (pin "43") (pinfunction "PE12_43") (pintype "bidirectional"))
      (node (ref "R14") (pin "2") (pinfunction "2_2") (pintype "passive"))
    )
    (net (code "41") (name "/MOM_DWN") (class "Default")
      (node (ref "IC3") (pin "56") (pinfunction "PD9_56") (pintype "bidirectional"))
      (node (ref "S4") (pin "B2") (pinfunction "2_B2") (pintype "passive"))
    )
    (net (code "42") (name "/MOM_RIGHT") (class "Default")
      (node (ref "IC3") (pin "55") (pinfunction "PD8_55") (pintype "bidirectional"))
      (node (ref "S3") (pin "B2") (pinfunction "2_B2") (pintype "passive"))
    )
    (net (code "43") (name "/NRST") (class "Default")
      (node (ref "IC3") (pin "14") (pinfunction "~{NRST}_14") (pintype "bidirectional"))
      (node (ref "J3") (pin "10") (pinfunction "NRST_10") (pintype "bidirectional"))
      (node (ref "JP4") (pin "3") (pinfunction "RST_3") (pintype "output"))
    )
    (net (code "44") (name "/OCS32_IN") (class "Default")
      (node (ref "C23") (pin "2") (pinfunction "2_2") (pintype "passive"))
      (node (ref "IC3") (pin "8") (pinfunction "PC14/OSC32_IN_8") (pintype "bidirectional"))
      (node (ref "X3") (pin "P$1") (pinfunction "1_P$1") (pintype "bidirectional"))
    )
    (net (code "45") (name "/OCS32_OUT") (class "Default")
      (node (ref "C24") (pin "2") (pinfunction "2_2") (pintype "passive"))
      (node (ref "IC3") (pin "9") (pinfunction "PC15/OSC32_OUT_9") (pintype "bidirectional"))
      (node (ref "X3") (pin "P$2") (pinfunction "2_P$2") (pintype "bidirectional"))
    )
    (net (code "46") (name "/PB11") (class "Default")
      (node (ref "C9") (pin "2") (pinfunction "2_2") (pintype "passive"))
      (node (ref "IC3") (pin "48") (pinfunction "VCAP1_48") (pintype "bidirectional"))
      (node (ref "JP1") (pin "7") (pinfunction "7_7") (pintype "passive"))
    )
    (net (code "47") (name "/SDIO_CLK") (class "Default")
      (node (ref "IC3") (pin "80") (pinfunction "PC12_80") (pintype "bidirectional"))
      (node (ref "U1") (pin "5") (pinfunction "CLK_5") (pintype "bidirectional"))
    )
    (net (code "48") (name "/SDIO_CMD") (class "Default")
      (node (ref "IC3") (pin "83") (pinfunction "PD2_83") (pintype "bidirectional"))
      (node (ref "U1") (pin "3") (pinfunction "CMD_3") (pintype "bidirectional"))
    )
    (net (code "49") (name "/SDIO_D0") (class "Default")
      (node (ref "IC3") (pin "65") (pinfunction "PC8_65") (pintype "bidirectional"))
      (node (ref "U1") (pin "7") (pinfunction "DAT0_7") (pintype "bidirectional"))
    )
    (net (code "50") (name "/SDIO_D1") (class "Default")
      (node (ref "IC3") (pin "66") (pinfunction "PC9_66") (pintype "bidirectional"))
      (node (ref "U1") (pin "8") (pinfunction "DAT1_8") (pintype "bidirectional"))
    )
    (net (code "51") (name "/SDIO_D2") (class "Default")
      (node (ref "IC3") (pin "78") (pinfunction "PC10_78") (pintype "bidirectional"))
      (node (ref "U1") (pin "1") (pinfunction "DAT2_1") (pintype "bidirectional"))
    )
    (net (code "52") (name "/SDIO_D3") (class "Default")
      (node (ref "IC3") (pin "79") (pinfunction "PC11_79") (pintype "bidirectional"))
      (node (ref "U1") (pin "2") (pinfunction "DAT3_2") (pintype "bidirectional"))
    )
    (net (code "53") (name "/SDIO_SW") (class "Default")
      (node (ref "IC3") (pin "67") (pinfunction "PA8_67") (pintype "bidirectional"))
      (node (ref "U1") (pin "CD") (pinfunction "DET_CD") (pintype "bidirectional"))
    )
    (net (code "54") (name "/SPI1_MISO") (class "Default")
      (node (ref "IC3") (pin "31") (pinfunction "PA6_31") (pintype "bidirectional"))
      (node (ref "IC6") (pin "7") (pinfunction "SPI_DOUT_7") (pintype "output"))
    )
    (net (code "55") (name "/SPI1_MOSI") (class "Default")
      (node (ref "IC3") (pin "32") (pinfunction "PA7_32") (pintype "bidirectional"))
      (node (ref "IC6") (pin "6") (pinfunction "SPI_DIN_6") (pintype "input"))
    )
    (net (code "56") (name "/SPI1_NSS") (class "Default")
      (node (ref "IC3") (pin "29") (pinfunction "PA4_29") (pintype "bidirectional"))
      (node (ref "IC6") (pin "8") (pinfunction "~{SPI_CS}_8") (pintype "input"))
    )
    (net (code "57") (name "/SPI1_SCK") (class "Default")
      (node (ref "IC3") (pin "30") (pinfunction "PA5_30") (pintype "bidirectional"))
      (node (ref "IC6") (pin "5") (pinfunction "SPI_CLK_5") (pintype "input"))
    )
    (net (code "58") (name "/SPI2_CLK") (class "Default")
      (node (ref "IC3") (pin "47") (pinfunction "PB10_47") (pintype "bidirectional"))
      (node (ref "JP1") (pin "8") (pinfunction "8_8") (pintype "passive"))
    )
    (net (code "59") (name "/SPI2_MISO") (class "Default")
      (node (ref "IC3") (pin "53") (pinfunction "PB14_53") (pintype "bidirectional"))
      (node (ref "JP1") (pin "9") (pinfunction "9_9") (pintype "passive"))
    )
    (net (code "60") (name "/SPI2_MOSI") (class "Default")
      (node (ref "IC3") (pin "54") (pinfunction "PB15_54") (pintype "bidirectional"))
      (node (ref "JP1") (pin "10") (pinfunction "10_10") (pintype "passive"))
    )
    (net (code "61") (name "/SPI2_NSS") (class "Default")
      (node (ref "IC3") (pin "51") (pinfunction "PB12_51") (pintype "bidirectional"))
      (node (ref "JP1") (pin "6") (pinfunction "6_6") (pintype "passive"))
    )
    (net (code "62") (name "/SPI3_MISO") (class "Default")
      (node (ref "IC3") (pin "90") (pinfunction "PB4_90") (pintype "bidirectional"))
      (node (ref "J2") (pin "33") (pinfunction "SDO_33") (pintype "output"))
    )
    (net (code "63") (name "/SPI3_MOSI") (class "Default")
      (node (ref "IC3") (pin "91") (pinfunction "PB5_91") (pintype "bidirectional"))
      (node (ref "J2") (pin "34") (pinfunction "SDI_34") (pintype "input"))
    )
    (net (code "64") (name "/SPI3_SCK") (class "Default")
      (node (ref "IC3") (pin "89") (pinfunction "PB3_89") (pintype "bidirectional"))
      (node (ref "J2") (pin "37") (pinfunction "D/CX(SCL)_37") (pintype "input"))
      (node (ref "R24") (pin "1") (pinfunction "1_1") (pintype "passive"))
    )
    (net (code "65") (name "/SWCLK") (class "Default")
      (node (ref "IC3") (pin "76") (pinfunction "PA14_76") (pintype "bidirectional"))
      (node (ref "J3") (pin "4") (pinfunction "SWCLK_4") (pintype "bidirectional"))
      (node (ref "JP4") (pin "4") (pinfunction "SWCLK_4") (pintype "output"))
    )
    (net (code "66") (name "/SWDAT") (class "Default")
      (node (ref "IC3") (pin "72") (pinfunction "PA13_72") (pintype "bidirectional"))
      (node (ref "J3") (pin "2") (pinfunction "SWDAT_2") (pintype "bidirectional"))
      (node (ref "JP4") (pin "2") (pinfunction "SWDAT_2") (pintype "bidirectional"))
    )
    (net (code "67") (name "/TEAR") (class "Default")
      (node (ref "IC3") (pin "4") (pinfunction "PE5_4") (pintype "bidirectional"))
      (node (ref "J2") (pin "39") (pinfunction "TE_39") (pintype "output"))
      (node (ref "TP21") (pin "TP") (pinfunction "TP_TP") (pintype "input"))
    )
    (net (code "68") (name "/TIM1_CH1N") (class "Default")
      (node (ref "IC3") (pin "52") (pinfunction "PB13_52") (pintype "bidirectional"))
      (node (ref "Q3") (pin "3") (pinfunction "G_3") (pintype "bidirectional"))
    )
    (net (code "69") (name "/TIM1_CH2") (class "Default")
      (node (ref "IC3") (pin "42") (pinfunction "PE11_42") (pintype "bidirectional"))
      (node (ref "JP2") (pin "8") (pinfunction "8_8") (pintype "passive"))
    )
    (net (code "70") (name "/TIM1_CH3") (class "Default")
      (node (ref "IC3") (pin "44") (pinfunction "PE13_44") (pintype "bidirectional"))
      (node (ref "JP2") (pin "9") (pinfunction "9_9") (pintype "passive"))
    )
    (net (code "71") (name "/TIM1_CH4") (class "Default")
      (node (ref "IC3") (pin "45") (pinfunction "PE14_45") (pintype "bidirectional"))
      (node (ref "JP2") (pin "10") (pinfunction "10_10") (pintype "passive"))
    )
    (net (code "72") (name "/TIM2_CH1") (class "Default")
      (node (ref "IC3") (pin "23") (pinfunction "PA0_23") (pintype "bidirectional"))
      (node (ref "JP1") (pin "2") (pinfunction "2_2") (pintype "passive"))
      (node (ref "OUTLINE1") (pin "CH4") (pinfunction "CH4_CH4") (pintype "bidirectional"))
      (node (ref "SV3") (pin "3") (pinfunction "3_3") (pintype "passive"))
    )
    (net (code "73") (name "/TIM2_CH2") (class "Default")
      (node (ref "IC3") (pin "24") (pinfunction "PA1_24") (pintype "bidirectional"))
      (node (ref "JP1") (pin "3") (pinfunction "3_3") (pintype "passive"))
      (node (ref "OUTLINE1") (pin "CH3") (pinfunction "CH3_CH3") (pintype "bidirectional"))
      (node (ref "SV5") (pin "3") (pinfunction "3_3") (pintype "passive"))
    )
    (net (code "74") (name "/TIM2_CH3") (class "Default")
      (node (ref "IC3") (pin "25") (pinfunction "PA2_25") (pintype "bidirectional"))
      (node (ref "JP1") (pin "4") (pinfunction "4_4") (pintype "passive"))
      (node (ref "OUTLINE1") (pin "CH2") (pinfunction "CH2_CH2") (pintype "bidirectional"))
      (node (ref "SV6") (pin "3") (pinfunction "3_3") (pintype "passive"))
    )
    (net (code "75") (name "/TIM2_CH4") (class "Default")
      (node (ref "IC3") (pin "26") (pinfunction "PA3_26") (pintype "bidirectional"))
      (node (ref "JP1") (pin "5") (pinfunction "5_5") (pintype "passive"))
      (node (ref "OUTLINE1") (pin "CH1") (pinfunction "CH1_CH1") (pintype "bidirectional"))
      (node (ref "SV4") (pin "3") (pinfunction "3_3") (pintype "passive"))
    )
    (net (code "76") (name "/TIM17_CH1") (class "Default")
      (node (ref "IC3") (pin "98") (pinfunction "PE1_98") (pintype "bidirectional"))
      (node (ref "Q8") (pin "3") (pinfunction "G_3") (pintype "bidirectional"))
    )
    (net (code "77") (name "/USART1_RX") (class "Default")
      (node (ref "IC3") (pin "93") (pinfunction "PB7_93") (pintype "bidirectional"))
      (node (ref "IC6") (pin "46") (pinfunction "UART1_TX_46") (pintype "output"))
      (node (ref "SV7") (pin "3") (pinfunction "3_3") (pintype "passive"))
    )
    (net (code "78") (name "/USART1_TX") (class "Default")
      (node (ref "IC3") (pin "92") (pinfunction "PB6_92") (pintype "bidirectional"))
      (node (ref "IC6") (pin "47") (pinfunction "UART1_RX_47") (pintype "input"))
      (node (ref "SV7") (pin "2") (pinfunction "2_2") (pintype "passive"))
    )
    (net (code "79") (name "/USART3_RX") (class "Default")
      (node (ref "IC3") (pin "34") (pinfunction "PC5_34") (pintype "bidirectional"))
      (node (ref "JP2") (pin "6") (pinfunction "6_6") (pintype "passive"))
    )
    (net (code "80") (name "/USART3_TX") (class "Default")
      (node (ref "IC3") (pin "33") (pinfunction "PC4_33") (pintype "bidirectional"))
      (node (ref "JP2") (pin "5") (pinfunction "5_5") (pintype "passive"))
    )
    (net (code "81") (name "/USB_ID") (class "Default")
      (node (ref "IC1") (pin "4") (pinfunction "IO3_4") (pintype "bidirectional"))
      (node (ref "IC3") (pin "69") (pinfunction "PA10_69") (pintype "bidirectional"))
      (node (ref "J1") (pin "ID") (pinfunction "USBID_ID") (pintype "bidirectional"))
    )
    (net (code "82") (name "/VBATT_IN") (class "Default")
      (node (ref "C33") (pin "2") (pinfunction "2_2") (pintype "passive"))
      (node (ref "IC3") (pin "6") (pinfunction "VBAT_6") (pintype "bidirectional"))
      (node (ref "R21") (pin "1") (pinfunction "1_1") (pintype "passive"))
      (node (ref "R22") (pin "1") (pinfunction "1_1") (pintype "passive"))
    )
    (net (code "83") (name "/VBUS") (class "Default")
      (node (ref "C1") (pin "2") (pinfunction "2_2") (pintype "passive"))
      (node (ref "C4") (pin "+") (pinfunction "+_+") (pintype "passive"))
      (node (ref "D3") (pin "A") (pinfunction "A_A") (pintype "passive"))
      (node (ref "IC4") (pin "1") (pinfunction "IN_1") (pintype "power_in"))
      (node (ref "L2") (pin "2") (pinfunction "2_2") (pintype "passive"))
      (node (ref "LED5") (pin "A") (pinfunction "A_A") (pintype "passive"))
      (node (ref "R10") (pin "2") (pinfunction "2_2") (pintype "passive"))
      (node (ref "SJ1") (pin "2") (pinfunction "2_2") (pintype "passive"))
    )
    (net (code "84") (name "/V_UNREG") (class "Default")
      (node (ref "C6") (pin "1") (pinfunction "1_1") (pintype "passive"))
      (node (ref "D2") (pin "A") (pinfunction "A_A") (pintype "passive"))
      (node (ref "IC2") (pin "1") (pinfunction "EN_1") (pintype "input"))
      (node (ref "IC2") (pin "8") (pinfunction "VIN_8") (pintype "power_in"))
      (node (ref "JP2") (pin "2") (pinfunction "2_2") (pintype "passive"))
      (node (ref "OUTLINE1") (pin "VBATT") (pinfunction "VBATT_VBATT") (pintype "bidirectional"))
      (node (ref "Q6") (pin "1") (pinfunction "D_1") (pintype "bidirectional"))
      (node (ref "Q6") (pin "2") (pinfunction "D_2") (pintype "bidirectional"))
      (node (ref "Q6") (pin "3") (pinfunction "D_3") (pintype "bidirectional"))
      (node (ref "R3") (pin "1") (pinfunction "1_1") (pintype "passive"))
      (node (ref "SV2") (pin "2") (pinfunction "2_2") (pintype "passive"))
      (node (ref "SV3") (pin "2") (pinfunction "2_2") (pintype "passive"))
      (node (ref "SV4") (pin "2") (pinfunction "2_2") (pintype "passive"))
      (node (ref "SV5") (pin "2") (pinfunction "2_2") (pintype "passive"))
      (node (ref "SV6") (pin "2") (pinfunction "2_2") (pintype "passive"))
    )
    (net (code "85") (name "/WS2812") (class "Default")
      (node (ref "D1") (pin "4") (pinfunction "DIN_4") (pintype "input"))
      (node (ref "IC3") (pin "37") (pinfunction "PB2_37") (pintype "bidirectional"))
      (node (ref "R11") (pin "2") (pinfunction "2_2") (pintype "passive"))
    )
    (net (code "86") (name "GND") (class "Default")
      (node (ref "C1") (pin "1") (pinfunction "1_1") (pintype "passive"))
      (node (ref "C10") (pin "1") (pinfunction "1_1") (pintype "passive"))
      (node (ref "C11") (pin "1") (pinfunction "1_1") (pintype "passive"))
      (node (ref "C12") (pin "1") (pinfunction "1_1") (pintype "passive"))
      (node (ref "C13") (pin "1") (pinfunction "1_1") (pintype "passive"))
      (node (ref "C15") (pin "1") (pinfunction "1_1") (pintype "passive"))
      (node (ref "C16") (pin "1") (pinfunction "1_1") (pintype "passive"))
      (node (ref "C17") (pin "1") (pinfunction "1_1") (pintype "passive"))
      (node (ref "C18") (pin "1") (pinfunction "1_1") (pintype "passive"))
      (node (ref "C19") (pin "1") (pinfunction "1_1") (pintype "passive"))
      (node (ref "C2") (pin "1") (pinfunction "1_1") (pintype "passive"))
      (node (ref "C20") (pin "1") (pinfunction "1_1") (pintype "passive"))
      (node (ref "C21") (pin "1") (pinfunction "1_1") (pintype "passive"))
      (node (ref "C22") (pin "1") (pinfunction "1_1") (pintype "passive"))
      (node (ref "C23") (pin "1") (pinfunction "1_1") (pintype "passive"))
      (node (ref "C24") (pin "1") (pinfunction "1_1") (pintype "passive"))
      (node (ref "C25") (pin "2") (pinfunction "2_2") (pintype "passive"))
      (node (ref "C26") (pin "2") (pinfunction "2_2") (pintype "passive"))
      (node (ref "C27") (pin "2") (pinfunction "2_2") (pintype "passive"))
      (node (ref "C29") (pin "1") (pinfunction "1_1") (pintype "passive"))
      (node (ref "C3") (pin "1") (pinfunction "1_1") (pintype "passive"))
      (node (ref "C33") (pin "1") (pinfunction "1_1") (pintype "passive"))
      (node (ref "C34") (pin "1") (pinfunction "1_1") (pintype "passive"))
      (node (ref "C35") (pin "2") (pinfunction "2_2") (pintype "passive"))
      (node (ref "C36") (pin "2") (pinfunction "2_2") (pintype "passive"))
      (node (ref "C37") (pin "1") (pinfunction "1_1") (pintype "passive"))
      (node (ref "C38") (pin "1") (pinfunction "1_1") (pintype "passive"))
      (node (ref "C39") (pin "1") (pinfunction "1_1") (pintype "passive"))
      (node (ref "C4") (pin "-") (pinfunction "-_-") (pintype "passive"))
      (node (ref "C40") (pin "2") (pinfunction "2_2") (pintype "passive"))
      (node (ref "C41") (pin "2") (pinfunction "2_2") (pintype "passive"))
      (node (ref "C42") (pin "2") (pinfunction "2_2") (pintype "passive"))
      (node (ref "C45") (pin "1") (pinfunction "1_1") (pintype "passive"))
      (node (ref "C5") (pin "2") (pinfunction "2_2") (pintype "passive"))
      (node (ref "C6") (pin "2") (pinfunction "2_2") (pintype "passive"))
      (node (ref "C7") (pin "1") (pinfunction "1_1") (pintype "passive"))
      (node (ref "C8") (pin "1") (pinfunction "1_1") (pintype "passive"))
      (node (ref "C9") (pin "1") (pinfunction "1_1") (pintype "passive"))
      (node (ref "D1") (pin "3") (pinfunction "VSS_3") (pintype "power_in"))
      (node (ref "IC1") (pin "3") (pinfunction "GND_3") (pintype "power_in"))
      (node (ref "IC2") (pin "2") (pinfunction "GND_2") (pintype "power_in"))
      (node (ref "IC2") (pin "3") (pinfunction "MODE_3") (pintype "input"))
      (node (ref "IC2") (pin "EP") (pinfunction "GND_EP") (pintype "power_in"))
      (node (ref "IC3") (pin "10") (pinfunction "VSS1_10") (pintype "bidirectional"))
      (node (ref "IC3") (pin "20") (pinfunction "VSSA/VREF-_20") (pintype "bidirectional"))
      (node (ref "IC3") (pin "27") (pinfunction "VSS2_27") (pintype "bidirectional"))
      (node (ref "IC3") (pin "74") (pinfunction "VSS3_74") (pintype "bidirectional"))
      (node (ref "IC3") (pin "99") (pinfunction "VSS4_99") (pintype "bidirectional"))
      (node (ref "IC4") (pin "3") (pinfunction "VSS_3") (pintype "power_in"))
      (node (ref "IC4") (pin "7") (pinfunction "ISET2_7") (pintype "input"))
      (node (ref "IC4") (pin "EP") (pinfunction "VSS_EP") (pintype "power_in"))
      (node (ref "IC6") (pin "1") (pinfunction "GND_1") (pintype "power_in"))
      (node (ref "IC6") (pin "16") (pinfunction "GND_16") (pintype "power_in"))
      (node (ref "IC6") (pin "2") (pinfunction "GND_2") (pintype "power_in"))
      (node (ref "IC6") (pin "27") (pinfunction "GND_27") (pintype "power_in"))
      (node (ref "IC6") (pin "28") (pinfunction "GND_28") (pintype "power_in"))
      (node (ref "IC6") (pin "30") (pinfunction "GND_30") (pintype "power_in"))
      (node (ref "IC6") (pin "32") (pinfunction "GND_32") (pintype "power_in"))
      (node (ref "IC6") (pin "38") (pinfunction "GND_38") (pintype "power_in"))
      (node (ref "IC6") (pin "43") (pinfunction "GND_43") (pintype "power_in"))
      (node (ref "IC6") (pin "55") (pinfunction "GND_55") (pintype "power_in"))
      (node (ref "IC6") (pin "56") (pinfunction "GND_56") (pintype "power_in"))
      (node (ref "IC6") (pin "57") (pinfunction "GND_57") (pintype "power_in"))
      (node (ref "IC6") (pin "58") (pinfunction "GND_58") (pintype "power_in"))
      (node (ref "IC6") (pin "59") (pinfunction "GND_59") (pintype "power_in"))
      (node (ref "IC6") (pin "60") (pinfunction "GND_60") (pintype "power_in"))
      (node (ref "IC6") (pin "61") (pinfunction "GND_61") (pintype "power_in"))
      (node (ref "IC6") (pin "62") (pinfunction "GND_62") (pintype "power_in"))
      (node (ref "IC6") (pin "63") (pinfunction "GND_63") (pintype "power_in"))
      (node (ref "IC8") (pin "1") (pinfunction "SDO/SA0_1") (pintype "bidirectional"))
      (node (ref "IC8") (pin "6") (pinfunction "GND_6") (pintype "power_in"))
      (node (ref "IC8") (pin "7") (pinfunction "GND_7") (pintype "power_in"))
      (node (ref "IC9") (pin "12") (pinfunction "GND_12") (pintype "power_in"))
      (node (ref "IC9") (pin "3") (pinfunction "GND_3") (pintype "power_in"))
      (node (ref "J1") (pin "GND") (pinfunction "GND_GND") (pintype "bidirectional"))
      (node (ref "J1") (pin "SHIELD") (pinfunction "SHIELD_SHIELD") (pintype "bidirectional"))
      (node (ref "J1") (pin "SHIELD@0") (pinfunction "SHIELD_SHIELD@0") (pintype "bidirectional"))
      (node (ref "J1") (pin "SHIELD@1") (pinfunction "SHIELD_SHIELD@1") (pintype "bidirectional"))
      (node (ref "J1") (pin "SHIELD@2") (pinfunction "SHIELD_SHIELD@2") (pintype "bidirectional"))
      (node (ref "J1") (pin "SHIELD@3") (pinfunction "SHIELD_SHIELD@3") (pintype "bidirectional"))
      (node (ref "J1") (pin "SHIELD@5") (pinfunction "SHIELD_SHIELD@5") (pintype "bidirectional"))
      (node (ref "J2") (pin "11") (pinfunction "VSYNC_11") (pintype "bidirectional"))
      (node (ref "J2") (pin "12") (pinfunction "HSYNC_12") (pintype "bidirectional"))
      (node (ref "J2") (pin "13") (pinfunction "DOTCLK_13") (pintype "bidirectional"))
      (node (ref "J2") (pin "14") (pinfunction "DE_14") (pintype "input"))
      (node (ref "J2") (pin "15") (pinfunction "DB17_15") (pintype "bidirectional"))
      (node (ref "J2") (pin "16") (pinfunction "DB16_16") (pintype "bidirectional"))
      (node (ref "J2") (pin "17") (pinfunction "DB15_17") (pintype "bidirectional"))
      (node (ref "J2") (pin "18") (pinfunction "DB14_18") (pintype "bidirectional"))
      (node (ref "J2") (pin "19") (pinfunction "DB13_19") (pintype "bidirectional"))
      (node (ref "J2") (pin "20") (pinfunction "DB12_20") (pintype "bidirectional"))
      (node (ref "J2") (pin "21") (pinfunction "DB11_21") (pintype "bidirectional"))
      (node (ref "J2") (pin "22") (pinfunction "DB10_22") (pintype "bidirectional"))
      (node (ref "J2") (pin "23") (pinfunction "DB9_23") (pintype "bidirectional"))
      (node (ref "J2") (pin "24") (pinfunction "DB8_24") (pintype "bidirectional"))
      (node (ref "J2") (pin "43") (pinfunction "GND_43") (pintype "power_in"))
      (node (ref "J2") (pin "48") (pinfunction "GND_48") (pintype "power_in"))
      (node (ref "J2") (pin "49") (pinfunction "GND_49") (pintype "power_in"))
      (node (ref "J2") (pin "50") (pinfunction "GND_50") (pintype "power_in"))
      (node (ref "J2") (pin "6") (pinfunction "IM0_6") (pintype "input"))
      (node (ref "J3") (pin "3") (pinfunction "GND1_3") (pintype "power_in"))
      (node (ref "J3") (pin "5") (pinfunction "GND2_5") (pintype "power_in"))
      (node (ref "J3") (pin "9") (pinfunction "GNDD_9") (pintype "power_in"))
      (node (ref "JP1") (pin "11") (pinfunction "11_11") (pintype "passive"))
      (node (ref "JP2") (pin "11") (pinfunction "11_11") (pintype "passive"))
      (node (ref "JP4") (pin "5") (pinfunction "GND_5") (pintype "power_in"))
      (node (ref "LED2") (pin "C") (pinfunction "C_C") (pintype "passive"))
      (node (ref "LED3") (pin "C") (pinfunction "C_C") (pintype "passive"))
      (node (ref "OUTLINE1") (pin "GND") (pinfunction "GND_GND") (pintype "bidirectional"))
      (node (ref "Q3") (pin "4") (pinfunction "S_4") (pintype "bidirectional"))
      (node (ref "Q3") (pin "EP2") (pinfunction "S_EP2") (pintype "bidirectional"))
      (node (ref "Q4") (pin "4") (pinfunction "S_4") (pintype "bidirectional"))
      (node (ref "Q8") (pin "4") (pinfunction "S_4") (pintype "bidirectional"))
      (node (ref "Q8") (pin "EP2") (pinfunction "S_EP2") (pintype "bidirectional"))
      (node (ref "R11") (pin "1") (pinfunction "1_1") (pintype "passive"))
      (node (ref "R13") (pin "2") (pinfunction "2_2") (pintype "passive"))
      (node (ref "R15") (pin "2") (pinfunction "2_2") (pintype "passive"))
      (node (ref "R16") (pin "2") (pinfunction "2_2") (pintype "passive"))
      (node (ref "R17") (pin "2") (pinfunction "2_2") (pintype "passive"))
      (node (ref "R20") (pin "2") (pinfunction "2_2") (pintype "passive"))
      (node (ref "R22") (pin "2") (pinfunction "2_2") (pintype "passive"))
      (node (ref "R27") (pin "2") (pinfunction "2_2") (pintype "passive"))
      (node (ref "R28") (pin "2") (pinfunction "2_2") (pintype "passive"))
      (node (ref "R33") (pin "1") (pinfunction "1_1") (pintype "passive"))
      (node (ref "R4") (pin "2") (pinfunction "2_2") (pintype "passive"))
      (node (ref "R5") (pin "2") (pinfunction "2_2") (pintype "passive"))
      (node (ref "R50") (pin "2") (pinfunction "2_2") (pintype "passive"))
      (node (ref "R6") (pin "2") (pinfunction "2_2") (pintype "passive"))
      (node (ref "R9") (pin "2") (pinfunction "2_2") (pintype "passive"))
      (node (ref "S3") (pin "A2") (pinfunction "1_A2") (pintype "passive"))
      (node (ref "S4") (pin "A2") (pinfunction "1_A2") (pintype "passive"))
      (node (ref "S5") (pin "2") (pinfunction "P_2") (pintype "passive"))
      (node (ref "S7") (pin "1") (pinfunction "1_1") (pintype "passive"))
      (node (ref "S8") (pin "2") (pinfunction "2_2") (pintype "passive"))
      (node (ref "SG1") (pin "P$2") (pinfunction "2_P$2") (pintype "passive"))
      (node (ref "SV2") (pin "1") (pinfunction "1_1") (pintype "passive"))
      (node (ref "SV3") (pin "1") (pinfunction "1_1") (pintype "passive"))
      (node (ref "SV4") (pin "1") (pinfunction "1_1") (pintype "passive"))
      (node (ref "SV5") (pin "1") (pinfunction "1_1") (pintype "passive"))
      (node (ref "SV6") (pin "1") (pinfunction "1_1") (pintype "passive"))
      (node (ref "SV7") (pin "1") (pinfunction "1_1") (pintype "passive"))
      (node (ref "U1") (pin "6") (pinfunction "GND_6") (pintype "bidirectional"))
      (node (ref "U1") (pin "GND") (pinfunction "SHIELD_GND") (pintype "bidirectional"))
      (node (ref "U1") (pin "GND1") (pinfunction "SHIELD_GND1") (pintype "bidirectional"))
      (node (ref "U1") (pin "GND2") (pinfunction "SHIELD_GND2") (pintype "bidirectional"))
      (node (ref "U1") (pin "GND3") (pinfunction "SHIELD_GND3") (pintype "bidirectional"))
      (node (ref "U1") (pin "GND4") (pinfunction "SHIELD_GND4") (pintype "bidirectional"))
      (node (ref "U1") (pin "GND5") (pinfunction "SHIELD_GND5") (pintype "bidirectional"))
      (node (ref "U1") (pin "GND6") (pinfunction "SHIELD_GND6") (pintype "bidirectional"))
      (node (ref "U1") (pin "GND7") (pinfunction "SHIELD_GND7") (pintype "bidirectional"))
      (node (ref "X2") (pin "2") (pinfunction "GND_2") (pintype "passive"))
      (node (ref "X2") (pin "4") (pinfunction "GND_4") (pintype "passive"))
    )
    (net (code "87") (name "Net-(ANT1-1)") (class "Default")
      (node (ref "ANT1") (pin "P$1") (pinfunction "1_P$1") (pintype "passive"))
      (node (ref "IC6") (pin "31") (pinfunction "RF_BG_31") (pintype "bidirectional"))
    )
    (net (code "88") (name "Net-(D1-DOUT)") (class "Default")
      (node (ref "D1") (pin "2") (pinfunction "DOUT_2") (pintype "output"))
      (node (ref "SV2") (pin "3") (pinfunction "3_3") (pintype "passive"))
    )
    (net (code "89") (name "Net-(D2-PadC)") (class "Default")
      (node (ref "D2") (pin "C") (pinfunction "C_C") (pintype "passive"))
      (node (ref "SJ1") (pin "1") (pinfunction "1_1") (pintype "passive"))
    )
    (net (code "90") (name "Net-(IC1-IO1)") (class "Default")
      (node (ref "IC1") (pin "1") (pinfunction "IO1_1") (pintype "bidirectional"))
      (node (ref "J1") (pin "D-") (pinfunction "D-_D-") (pintype "bidirectional"))
      (node (ref "R23") (pin "2") (pinfunction "2_2") (pintype "passive"))
    )
    (net (code "91") (name "Net-(IC1-IO2)") (class "Default")
      (node (ref "IC1") (pin "2") (pinfunction "IO2_2") (pintype "bidirectional"))
      (node (ref "J1") (pin "D+") (pinfunction "D+_D+") (pintype "bidirectional"))
      (node (ref "R25") (pin "2") (pinfunction "2_2") (pintype "passive"))
    )
    (net (code "92") (name "Net-(IC1-VCC)") (class "Default")
      (node (ref "C7") (pin "2") (pinfunction "2_2") (pintype "passive"))
      (node (ref "IC1") (pin "5") (pinfunction "VCC_5") (pintype "power_in"))
      (node (ref "J1") (pin "VBUS") (pinfunction "VBUS_VBUS") (pintype "bidirectional"))
      (node (ref "L2") (pin "1") (pinfunction "1_1") (pintype "passive"))
    )
    (net (code "93") (name "Net-(IC2-SW)") (class "Default")
      (node (ref "IC2") (pin "7") (pinfunction "SW_7") (pintype "output"))
      (node (ref "L1") (pin "1") (pinfunction "1_1") (pintype "passive"))
    )
    (net (code "94") (name "Net-(IC3F-PH0{slash}OCS_IN)") (class "Default")
      (node (ref "C21") (pin "2") (pinfunction "2_2") (pintype "passive"))
      (node (ref "IC3") (pin "12") (pinfunction "PH0/OCS_IN_12") (pintype "bidirectional"))
      (node (ref "X2") (pin "3") (pinfunction "C2_3") (pintype "passive"))
    )
    (net (code "95") (name "Net-(IC3F-PH1{slash}OSC_OUT)") (class "Default")
      (node (ref "IC3") (pin "13") (pinfunction "PH1/OSC_OUT_13") (pintype "bidirectional"))
      (node (ref "R43") (pin "1") (pinfunction "1_1") (pintype "passive"))
    )
    (net (code "96") (name "Net-(IC3G-VCAP2)") (class "Default")
      (node (ref "C29") (pin "2") (pinfunction "2_2") (pintype "passive"))
      (node (ref "IC3") (pin "73") (pinfunction "VCAP2_73") (pintype "bidirectional"))
      (node (ref "R7") (pin "2") (pinfunction "2_2") (pintype "passive"))
    )
    (net (code "97") (name "Net-(IC3G-VDD2)") (class "Default")
      (node (ref "C19") (pin "2") (pinfunction "2_2") (pintype "passive"))
      (node (ref "IC3") (pin "19") (pinfunction "VDD2_19") (pintype "bidirectional"))
      (node (ref "R8") (pin "1") (pinfunction "1_1") (pintype "passive"))
    )
    (net (code "98") (name "Net-(IC3G-VDDA)") (class "Default")
      (node (ref "C15") (pin "2") (pinfunction "2_2") (pintype "passive"))
      (node (ref "C16") (pin "2") (pinfunction "2_2") (pintype "passive"))
      (node (ref "IC3") (pin "21") (pinfunction "VREF+_21") (pintype "bidirectional"))
      (node (ref "IC3") (pin "22") (pinfunction "VDDA_22") (pintype "bidirectional"))
      (node (ref "L3") (pin "2") (pinfunction "2_2") (pintype "passive"))
    )
    (net (code "99") (name "Net-(IC3G-VSS)") (class "Default")
      (node (ref "C10") (pin "2") (pinfunction "2_2") (pintype "passive"))
      (node (ref "IC3") (pin "49") (pinfunction "VSS_49") (pintype "bidirectional"))
    )
    (net (code "100") (name "Net-(IC4-ISET)") (class "Default")
      (node (ref "IC4") (pin "2") (pinfunction "ISET_2") (pintype "input"))
      (node (ref "R9") (pin "1") (pinfunction "1_1") (pintype "passive"))
    )
    (net (code "101") (name "Net-(IC4-PRETERM)") (class "Default")
      (node (ref "IC4") (pin "4") (pinfunction "PRETERM_4") (pintype "input"))
      (node (ref "R6") (pin "1") (pinfunction "1_1") (pintype "passive"))
    )
    (net (code "102") (name "Net-(IC4-TS)") (class "Default")
      (node (ref "IC4") (pin "9") (pinfunction "TS_9") (pintype "input"))
      (node (ref "R13") (pin "1") (pinfunction "1_1") (pintype "passive"))
    )
    (net (code "103") (name "Net-(IC4-~{CHG})") (class "Default")
      (node (ref "IC4") (pin "8") (pinfunction "~{CHG}_8") (pintype "output"))
      (node (ref "R2") (pin "1") (pinfunction "1_1") (pintype "passive"))
    )
    (net (code "104") (name "Net-(IC6-FORCE_AP)") (class "Default")
      (node (ref "IC6") (pin "10") (pinfunction "FORCE_AP_10") (pintype "bidirectional"))
      (node (ref "R27") (pin "1") (pinfunction "1_1") (pintype "passive"))
      (node (ref "TP11") (pin "TP") (pinfunction "TP_TP") (pintype "input"))
    )
    (net (code "105") (name "Net-(IC6-RESERVED)") (class "Default")
      (node (ref "IC6") (pin "21") (pinfunction "RESERVED_21") (pintype "input"))
      (node (ref "R20") (pin "1") (pinfunction "1_1") (pintype "passive"))
    )
    (net (code "106") (name "Net-(IC6-SOP2)") (class "Default")
      (node (ref "IC6") (pin "23") (pinfunction "SOP2_23") (pintype "bidirectional"))
      (node (ref "R17") (pin "1") (pinfunction "1_1") (pintype "passive"))
    )
    (net (code "107") (name "Net-(IC6-TEST_58)") (class "Default")
      (node (ref "IC6") (pin "48") (pinfunction "TEST_58_48") (pintype "output"))
      (node (ref "TP14") (pin "TP") (pinfunction "TP_TP") (pintype "input"))
    )
    (net (code "108") (name "Net-(IC6-TEST_59)") (class "Default")
      (node (ref "IC6") (pin "49") (pinfunction "TEST_59_49") (pintype "output"))
      (node (ref "TP15") (pin "TP") (pinfunction "TP_TP") (pintype "input"))
    )
    (net (code "109") (name "Net-(IC6-TEST_60)") (class "Default")
      (node (ref "IC6") (pin "50") (pinfunction "TEST_60_50") (pintype "output"))
      (node (ref "TP16") (pin "TP") (pinfunction "TP_TP") (pintype "input"))
    )
    (net (code "110") (name "Net-(IC6-TEST_62)") (class "Default")
      (node (ref "IC6") (pin "52") (pinfunction "TEST_62_52") (pintype "output"))
      (node (ref "TP17") (pin "TP") (pinfunction "TP_TP") (pintype "input"))
    )
    (net (code "111") (name "Net-(IC6-~{UART_CTS})") (class "Default")
      (node (ref "IC6") (pin "51") (pinfunction "~{UART_CTS}_51") (pintype "bidirectional"))
      (node (ref "TP12") (pin "TP") (pinfunction "TP_TP") (pintype "input"))
    )
    (net (code "112") (name "Net-(IC6-~{UART_RTS})") (class "Default")
      (node (ref "IC6") (pin "44") (pinfunction "~{UART_RTS}_44") (pintype "bidirectional"))
      (node (ref "TP13") (pin "TP") (pinfunction "TP_TP") (pintype "input"))
    )
    (net (code "113") (name "Net-(IC7-BAT)") (class "Default")
      (node (ref "C48") (pin "2") (pinfunction "2_2") (pintype "passive"))
      (node (ref "IC7") (pin "5") (pinfunction "BAT_5") (pintype "input"))
      (node (ref "R51") (pin "1") (pinfunction "1_1") (pintype "passive"))
    )
    (net (code "114") (name "Net-(IC7-COUT)") (class "Default")
      (node (ref "IC7") (pin "2") (pinfunction "COUT_2") (pintype "output"))
      (node (ref "Q4") (pin "5") (pinfunction "G_5") (pintype "bidirectional"))
      (node (ref "R28") (pin "1") (pinfunction "1_1") (pintype "passive"))
    )
    (net (code "115") (name "Net-(IC7-DOUT)") (class "Default")
      (node (ref "IC7") (pin "3") (pinfunction "DOUT_3") (pintype "output"))
      (node (ref "Q4") (pin "2") (pinfunction "G_2") (pintype "bidirectional"))
      (node (ref "R29") (pin "1") (pinfunction "1_1") (pintype "passive"))
    )
    (net (code "116") (name "Net-(IC7-V-)") (class "Default")
      (node (ref "IC7") (pin "6") (pinfunction "V-_6") (pintype "input"))
      (node (ref "R50") (pin "1") (pinfunction "1_1") (pintype "passive"))
    )
    (net (code "117") (name "Net-(IC7-VSS)") (class "Default")
      (node (ref "C48") (pin "1") (pinfunction "1_1") (pintype "passive"))
      (node (ref "IC7") (pin "4") (pinfunction "VSS_4") (pintype "power_in"))
      (node (ref "JP3") (pin "1") (pinfunction "1_1") (pintype "passive"))
      (node (ref "Q4") (pin "1") (pinfunction "S_1") (pintype "bidirectional"))
      (node (ref "R29") (pin "2") (pinfunction "2_2") (pintype "passive"))
    )
    (net (code "118") (name "Net-(IC8-INT2)") (class "Default")
      (node (ref "IC8") (pin "9") (pinfunction "INT2_9") (pintype "output"))
      (node (ref "IC9") (pin "8") (pinfunction "DRDY_8") (pintype "output"))
    )
    (net (code "119") (name "Net-(IC8-SCX)") (class "Default")
      (node (ref "IC8") (pin "3") (pinfunction "SCX_3") (pintype "input"))
      (node (ref "IC9") (pin "1") (pinfunction "SCL/SPC_1") (pintype "input"))
      (node (ref "R31") (pin "2") (pinfunction "2_2") (pintype "passive"))
    )
    (net (code "120") (name "Net-(IC8-SDX)") (class "Default")
      (node (ref "IC8") (pin "2") (pinfunction "SDX_2") (pintype "input"))
      (node (ref "IC9") (pin "11") (pinfunction "SDA/SDI/SDO_11") (pintype "bidirectional"))
      (node (ref "R30") (pin "2") (pinfunction "2_2") (pintype "passive"))
    )
    (net (code "121") (name "Net-(IC9-C1)") (class "Default")
      (node (ref "C40") (pin "1") (pinfunction "1_1") (pintype "passive"))
      (node (ref "IC9") (pin "4") (pinfunction "C1_4") (pintype "bidirectional"))
    )
    (net (code "122") (name "Net-(J2-LEDK1)") (class "Default")
      (node (ref "J2") (pin "2") (pinfunction "LEDK1_2") (pintype "passive"))
      (node (ref "R47") (pin "2") (pinfunction "2_2") (pintype "passive"))
    )
    (net (code "123") (name "Net-(J2-LEDK2)") (class "Default")
      (node (ref "J2") (pin "3") (pinfunction "LEDK2_3") (pintype "passive"))
      (node (ref "R48") (pin "2") (pinfunction "2_2") (pintype "passive"))
    )
    (net (code "124") (name "Net-(J2-LEDK3)") (class "Default")
      (node (ref "J2") (pin "4") (pinfunction "LEDK3_4") (pintype "passive"))
      (node (ref "R49") (pin "2") (pinfunction "2_2") (pintype "passive"))
    )
    (net (code "125") (name "Net-(J2-LEDK4)") (class "Default")
      (node (ref "J2") (pin "5") (pinfunction "LEDK4_5") (pintype "passive"))
      (node (ref "R44") (pin "2") (pinfunction "2_2") (pintype "passive"))
    )
    (net (code "126") (name "Net-(LED1-PadA)") (class "Default")
      (node (ref "LED1") (pin "A") (pinfunction "A_A") (pintype "passive"))
      (node (ref "R1") (pin "1") (pinfunction "1_1") (pintype "passive"))
    )
    (net (code "127") (name "Net-(LED2-PadA)") (class "Default")
      (node (ref "LED2") (pin "A") (pinfunction "A_A") (pintype "passive"))
      (node (ref "R12") (pin "1") (pinfunction "1_1") (pintype "passive"))
    )
    (net (code "128") (name "Net-(LED3-PadA)") (class "Default")
      (node (ref "LED3") (pin "A") (pinfunction "A_A") (pintype "passive"))
      (node (ref "R14") (pin "1") (pinfunction "1_1") (pintype "passive"))
    )
    (net (code "129") (name "Net-(LED5-PadC)") (class "Default")
      (node (ref "LED5") (pin "C") (pinfunction "C_C") (pintype "passive"))
      (node (ref "R2") (pin "2") (pinfunction "2_2") (pintype "passive"))
    )
    (net (code "130") (name "Net-(Q1-B1)") (class "Default")
      (node (ref "Q1") (pin "1") (pinfunction "C1_1") (pintype "passive"))
      (node (ref "Q1") (pin "2") (pinfunction "B1_2") (pintype "passive"))
      (node (ref "Q1") (pin "3") (pinfunction "B2_3") (pintype "passive"))
      (node (ref "R16") (pin "1") (pinfunction "1_1") (pintype "passive"))
    )
    (net (code "131") (name "Net-(Q1-C2)") (class "Default")
      (node (ref "Q1") (pin "4") (pinfunction "C2_4") (pintype "passive"))
      (node (ref "Q2") (pin "4") (pinfunction "G_4") (pintype "bidirectional"))
      (node (ref "R15") (pin "1") (pinfunction "1_1") (pintype "passive"))
    )
    (net (code "132") (name "Net-(Q1-E2)") (class "Default")
      (node (ref "D3") (pin "C") (pinfunction "C_C") (pintype "passive"))
      (node (ref "Q1") (pin "5") (pinfunction "E2_5") (pintype "passive"))
      (node (ref "Q2") (pin "5") (pinfunction "S_5") (pintype "bidirectional"))
      (node (ref "Q2") (pin "6") (pinfunction "S_6") (pintype "bidirectional"))
      (node (ref "Q2") (pin "7") (pinfunction "S_7") (pintype "bidirectional"))
      (node (ref "Q2") (pin "8") (pinfunction "S_8") (pintype "bidirectional"))
      (node (ref "Q2") (pin "EP") (pinfunction "S_EP") (pintype "bidirectional"))
      (node (ref "Q6") (pin "5") (pinfunction "S_5") (pintype "bidirectional"))
      (node (ref "Q6") (pin "6") (pinfunction "S_6") (pintype "bidirectional"))
      (node (ref "Q6") (pin "7") (pinfunction "S_7") (pintype "bidirectional"))
      (node (ref "Q6") (pin "8") (pinfunction "S_8") (pintype "bidirectional"))
      (node (ref "Q6") (pin "EP") (pinfunction "S_EP") (pintype "bidirectional"))
      (node (ref "R45") (pin "1") (pinfunction "1_1") (pintype "passive"))
    )
    (net (code "133") (name "Net-(Q4A-D-Pad6)") (class "Default")
      (node (ref "Q4") (pin "3") (pinfunction "D_3") (pintype "bidirectional"))
      (node (ref "Q4") (pin "6") (pinfunction "D_6") (pintype "bidirectional"))
      (node (ref "Q4") (pin "EP1") (pinfunction "D_EP1") (pintype "bidirectional"))
      (node (ref "Q4") (pin "EP2") (pinfunction "D_EP2") (pintype "bidirectional"))
    )
    (net (code "134") (name "Net-(Q6-G)") (class "Default")
      (node (ref "Q6") (pin "4") (pinfunction "G_4") (pintype "bidirectional"))
      (node (ref "R45") (pin "2") (pinfunction "2_2") (pintype "passive"))
      (node (ref "S5") (pin "3") (pinfunction "S_3") (pintype "passive"))
    )
    (net (code "135") (name "Net-(Q8-D-Pad1)") (class "Default")
      (node (ref "Q8") (pin "1") (pinfunction "D_1") (pintype "bidirectional"))
      (node (ref "Q8") (pin "2") (pinfunction "D_2") (pintype "bidirectional"))
      (node (ref "Q8") (pin "5") (pinfunction "D_5") (pintype "bidirectional"))
      (node (ref "Q8") (pin "6") (pinfunction "D_6") (pintype "bidirectional"))
      (node (ref "Q8") (pin "EP1") (pinfunction "D_EP1") (pintype "bidirectional"))
      (node (ref "R44") (pin "1") (pinfunction "1_1") (pintype "passive"))
      (node (ref "R47") (pin "1") (pinfunction "1_1") (pintype "passive"))
      (node (ref "R48") (pin "1") (pinfunction "1_1") (pintype "passive"))
      (node (ref "R49") (pin "1") (pinfunction "1_1") (pintype "passive"))
    )
    (net (code "136") (name "Net-(SG1-1)") (class "Default")
      (node (ref "R26") (pin "1") (pinfunction "1_1") (pintype "passive"))
      (node (ref "SG1") (pin "P$1") (pinfunction "1_P$1") (pintype "passive"))
    )
    (net (code "137") (name "Net-(X2-C1)") (class "Default")
      (node (ref "C20") (pin "2") (pinfunction "2_2") (pintype "passive"))
      (node (ref "R43") (pin "2") (pinfunction "2_2") (pintype "passive"))
      (node (ref "X2") (pin "1") (pinfunction "C1_1") (pintype "passive"))
    )
    (net (code "138") (name "VBAT") (class "Default")
      (node (ref "C3") (pin "2") (pinfunction "2_2") (pintype "passive"))
      (node (ref "IC4") (pin "10") (pinfunction "OUT_10") (pintype "passive"))
      (node (ref "JP3") (pin "2") (pinfunction "2_2") (pintype "passive"))
      (node (ref "Q1") (pin "6") (pinfunction "E1_6") (pintype "passive"))
      (node (ref "Q2") (pin "1") (pinfunction "D_1") (pintype "bidirectional"))
      (node (ref "Q2") (pin "2") (pinfunction "D_2") (pintype "bidirectional"))
      (node (ref "Q2") (pin "3") (pinfunction "D_3") (pintype "bidirectional"))
      (node (ref "R21") (pin "2") (pinfunction "2_2") (pintype "passive"))
      (node (ref "R51") (pin "2") (pinfunction "2_2") (pintype "passive"))
    )
    (net (code "139") (name "unconnected-(IC2-FB-Pad4)") (class "Default")
      (node (ref "IC2") (pin "4") (pinfunction "FB_4") (pintype "input"))
    )
    (net (code "140") (name "unconnected-(IC2-PG-Pad6)") (class "Default")
      (node (ref "IC2") (pin "6") (pinfunction "PG_6") (pintype "bidirectional"))
    )
    (net (code "141") (name "unconnected-(IC3C-PC7-Pad64)") (class "Default")
      (node (ref "IC3") (pin "64") (pinfunction "PC7_64") (pintype "bidirectional"))
    )
    (net (code "142") (name "unconnected-(IC4-~{PG}-Pad5)") (class "Default")
      (node (ref "IC4") (pin "5") (pinfunction "~{PG}_5") (pintype "output"))
    )
    (net (code "143") (name "unconnected-(IC6-ANT_SEL_1-Pad25)") (class "Default")
      (node (ref "IC6") (pin "25") (pinfunction "ANT_SEL_1_25") (pintype "output"))
    )
    (net (code "144") (name "unconnected-(IC6-ANT_SEL_2-Pad26)") (class "Default")
      (node (ref "IC6") (pin "26") (pinfunction "ANT_SEL_2_26") (pintype "output"))
    )
    (net (code "145") (name "unconnected-(IC6-SOP0-Pad34)") (class "Default")
      (node (ref "IC6") (pin "34") (pinfunction "SOP0_34") (pintype "bidirectional"))
    )
    (net (code "146") (name "unconnected-(IC6-SOP1-Pad24)") (class "Default")
      (node (ref "IC6") (pin "24") (pinfunction "SOP1_24") (pintype "bidirectional"))
    )
    (net (code "147") (name "unconnected-(IC9-INT-Pad7)") (class "Default")
      (node (ref "IC9") (pin "7") (pinfunction "INT_7") (pintype "output"))
    )
    (net (code "148") (name "unconnected-(J2-X+-Pad44)") (class "Default")
      (node (ref "J2") (pin "44") (pinfunction "X+_44") (pintype "passive"))
    )
    (net (code "149") (name "unconnected-(J2-X--Pad46)") (class "Default")
      (node (ref "J2") (pin "46") (pinfunction "X-_46") (pintype "passive"))
    )
    (net (code "150") (name "unconnected-(J2-Y+-Pad45)") (class "Default")
      (node (ref "J2") (pin "45") (pinfunction "Y+_45") (pintype "passive"))
    )
    (net (code "151") (name "unconnected-(J2-Y--Pad47)") (class "Default")
      (node (ref "J2") (pin "47") (pinfunction "Y-_47") (pintype "passive"))
    )
    (net (code "152") (name "unconnected-(J3-KEY-Pad7)") (class "Default")
      (node (ref "J3") (pin "7") (pinfunction "KEY_7") (pintype "bidirectional"))
    )
    (net (code "153") (name "unconnected-(J3-NC-Pad8)") (class "Default")
      (node (ref "J3") (pin "8") (pinfunction "NC_8") (pintype "no_connect"))
    )
    (net (code "154") (name "unconnected-(J3-SWO-Pad6)") (class "Default")
      (node (ref "J3") (pin "6") (pinfunction "SWO_6") (pintype "bidirectional"))
    )
    (net (code "155") (name "unconnected-(JP4-SWO-Pad6)") (class "Default")
      (node (ref "JP4") (pin "6") (pinfunction "SWO_6") (pintype "input"))
    )
    (net (code "156") (name "unconnected-(S5-O-Pad1)") (class "Default")
      (node (ref "S5") (pin "1") (pinfunction "O_1") (pintype "passive"))
    )
  )
)
